# 001000-004.net
KiCad netlist of a schematic drawn in EAGLE
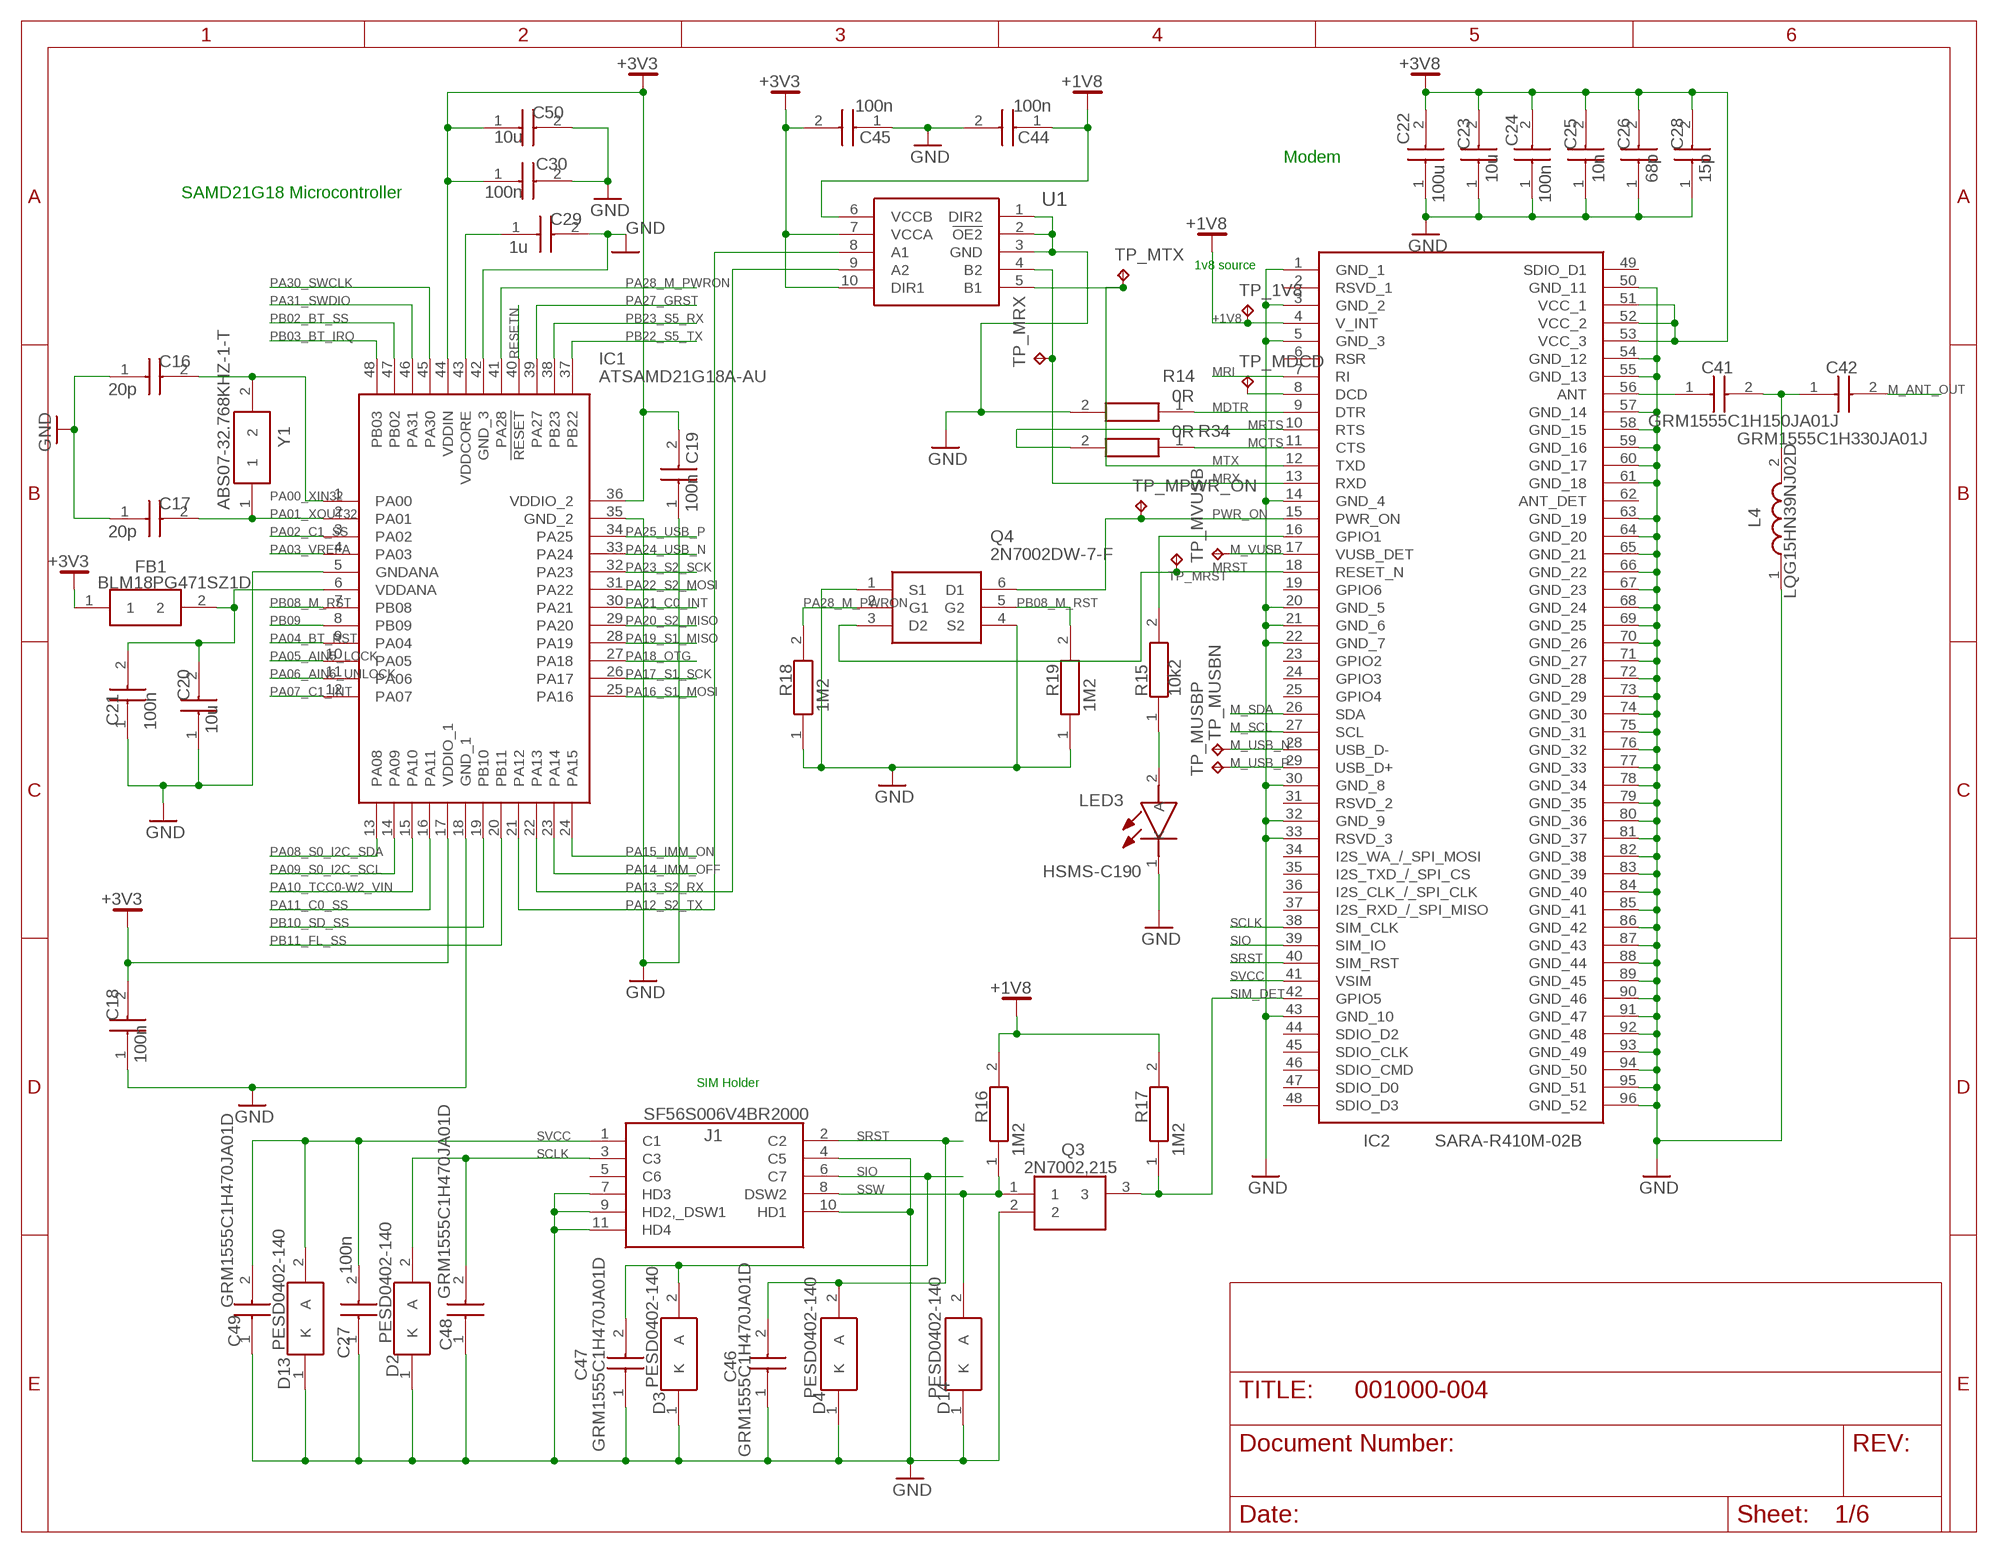
[diagram p0: schematic, sheet 1]
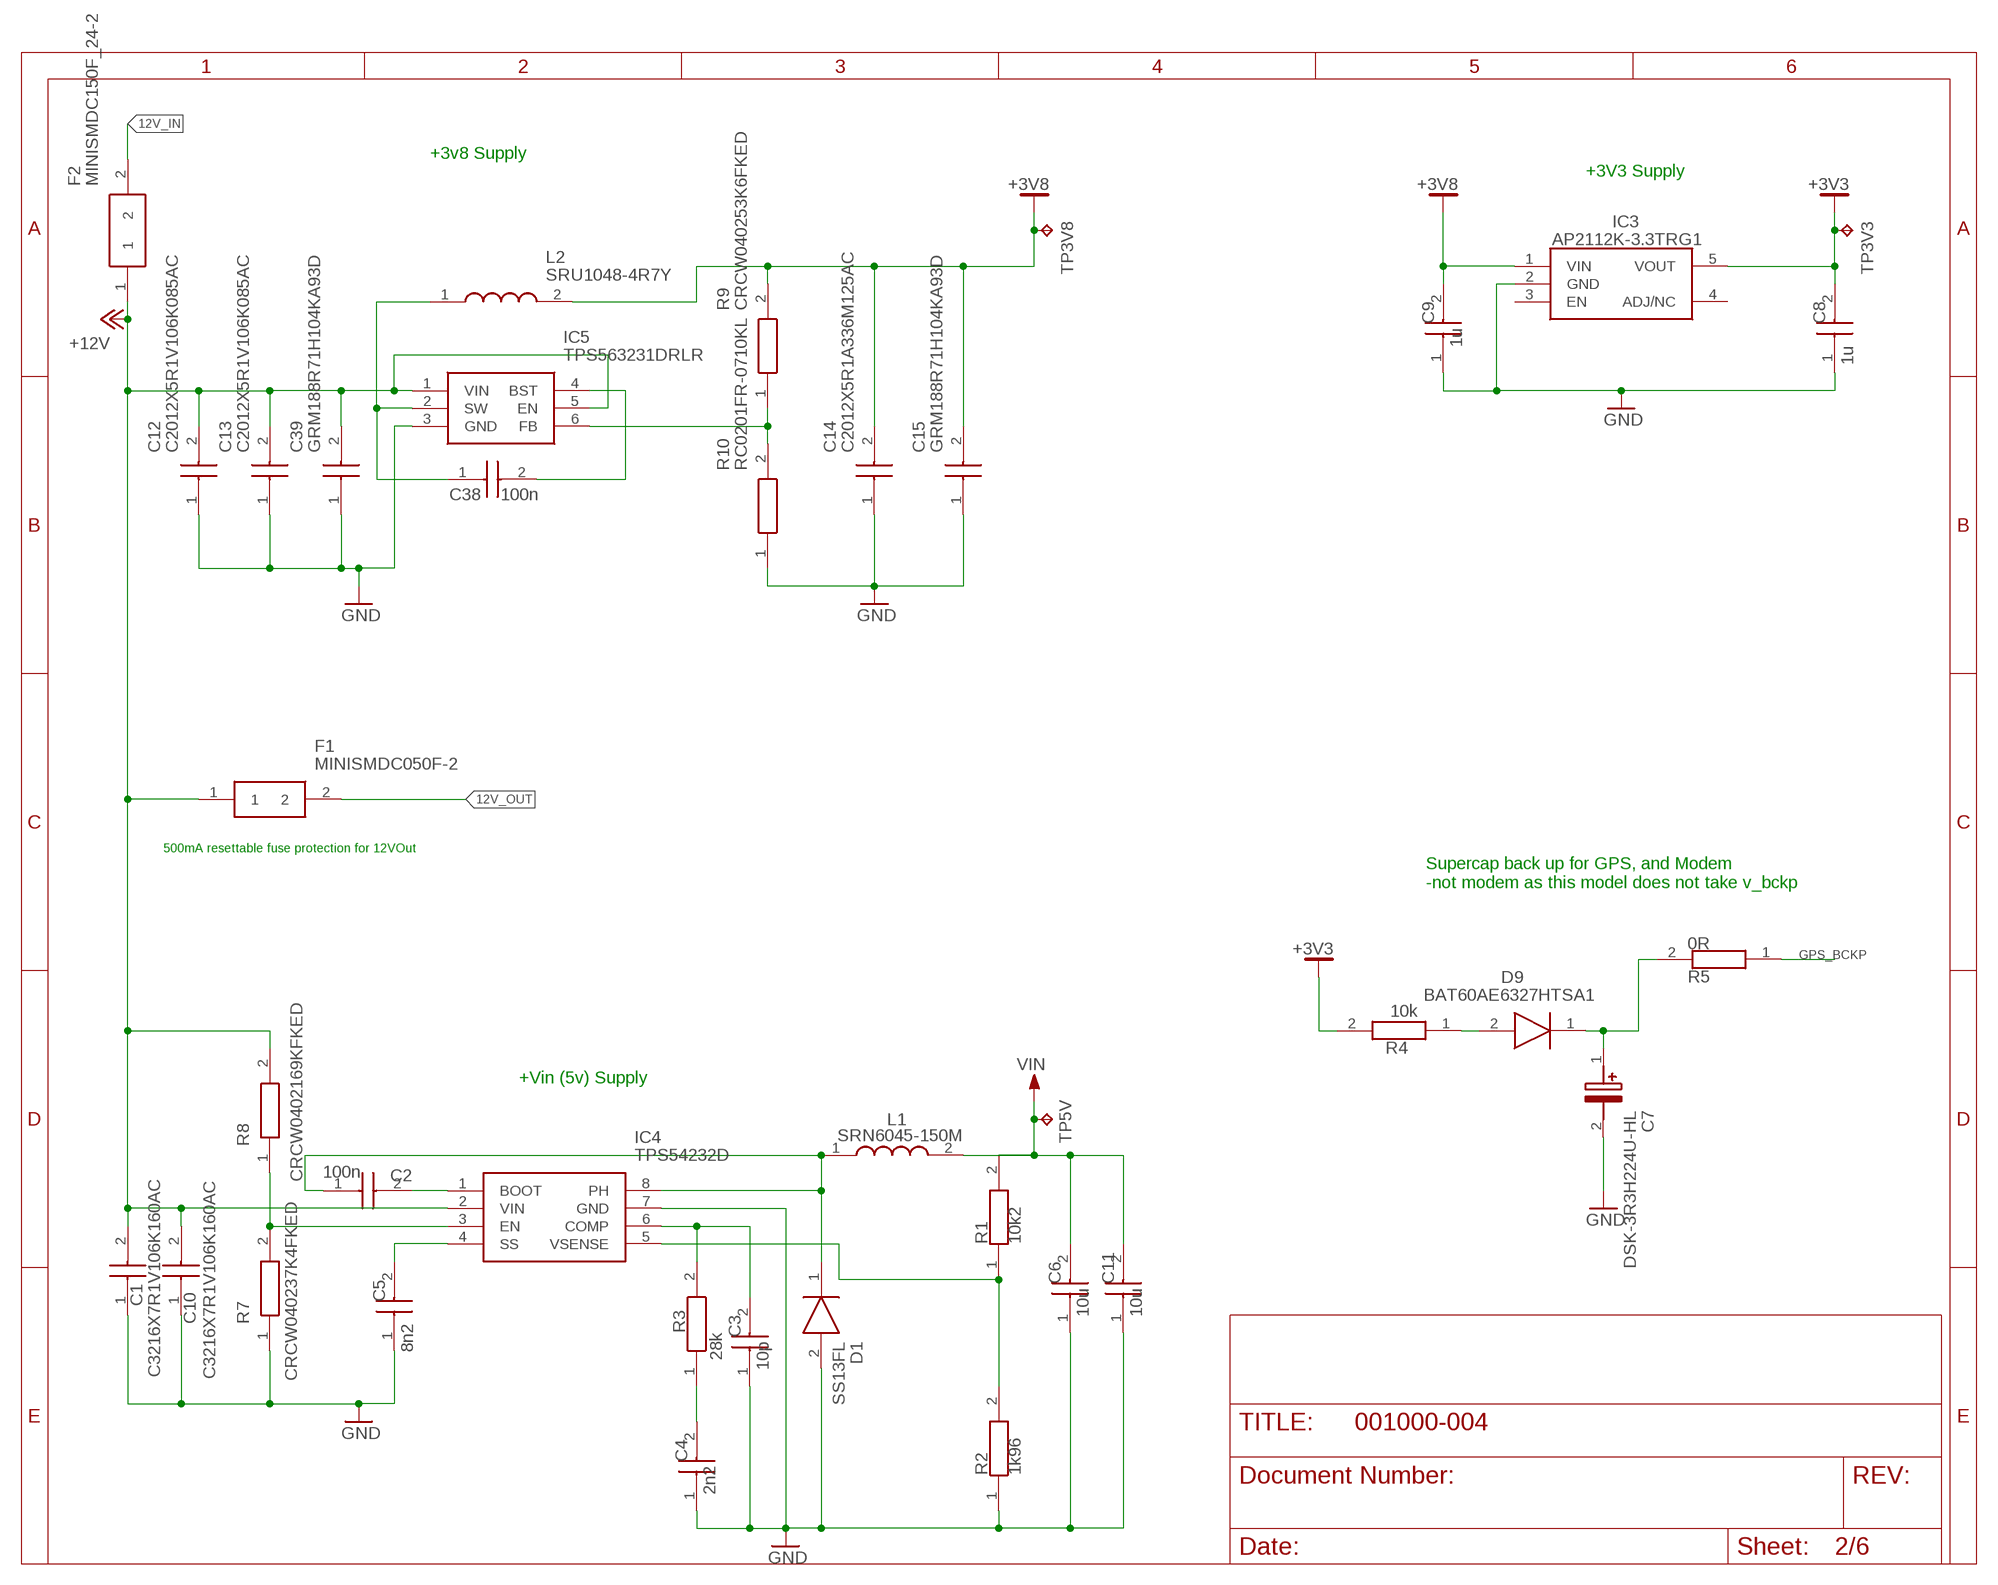
[diagram p1: schematic, sheet 2]
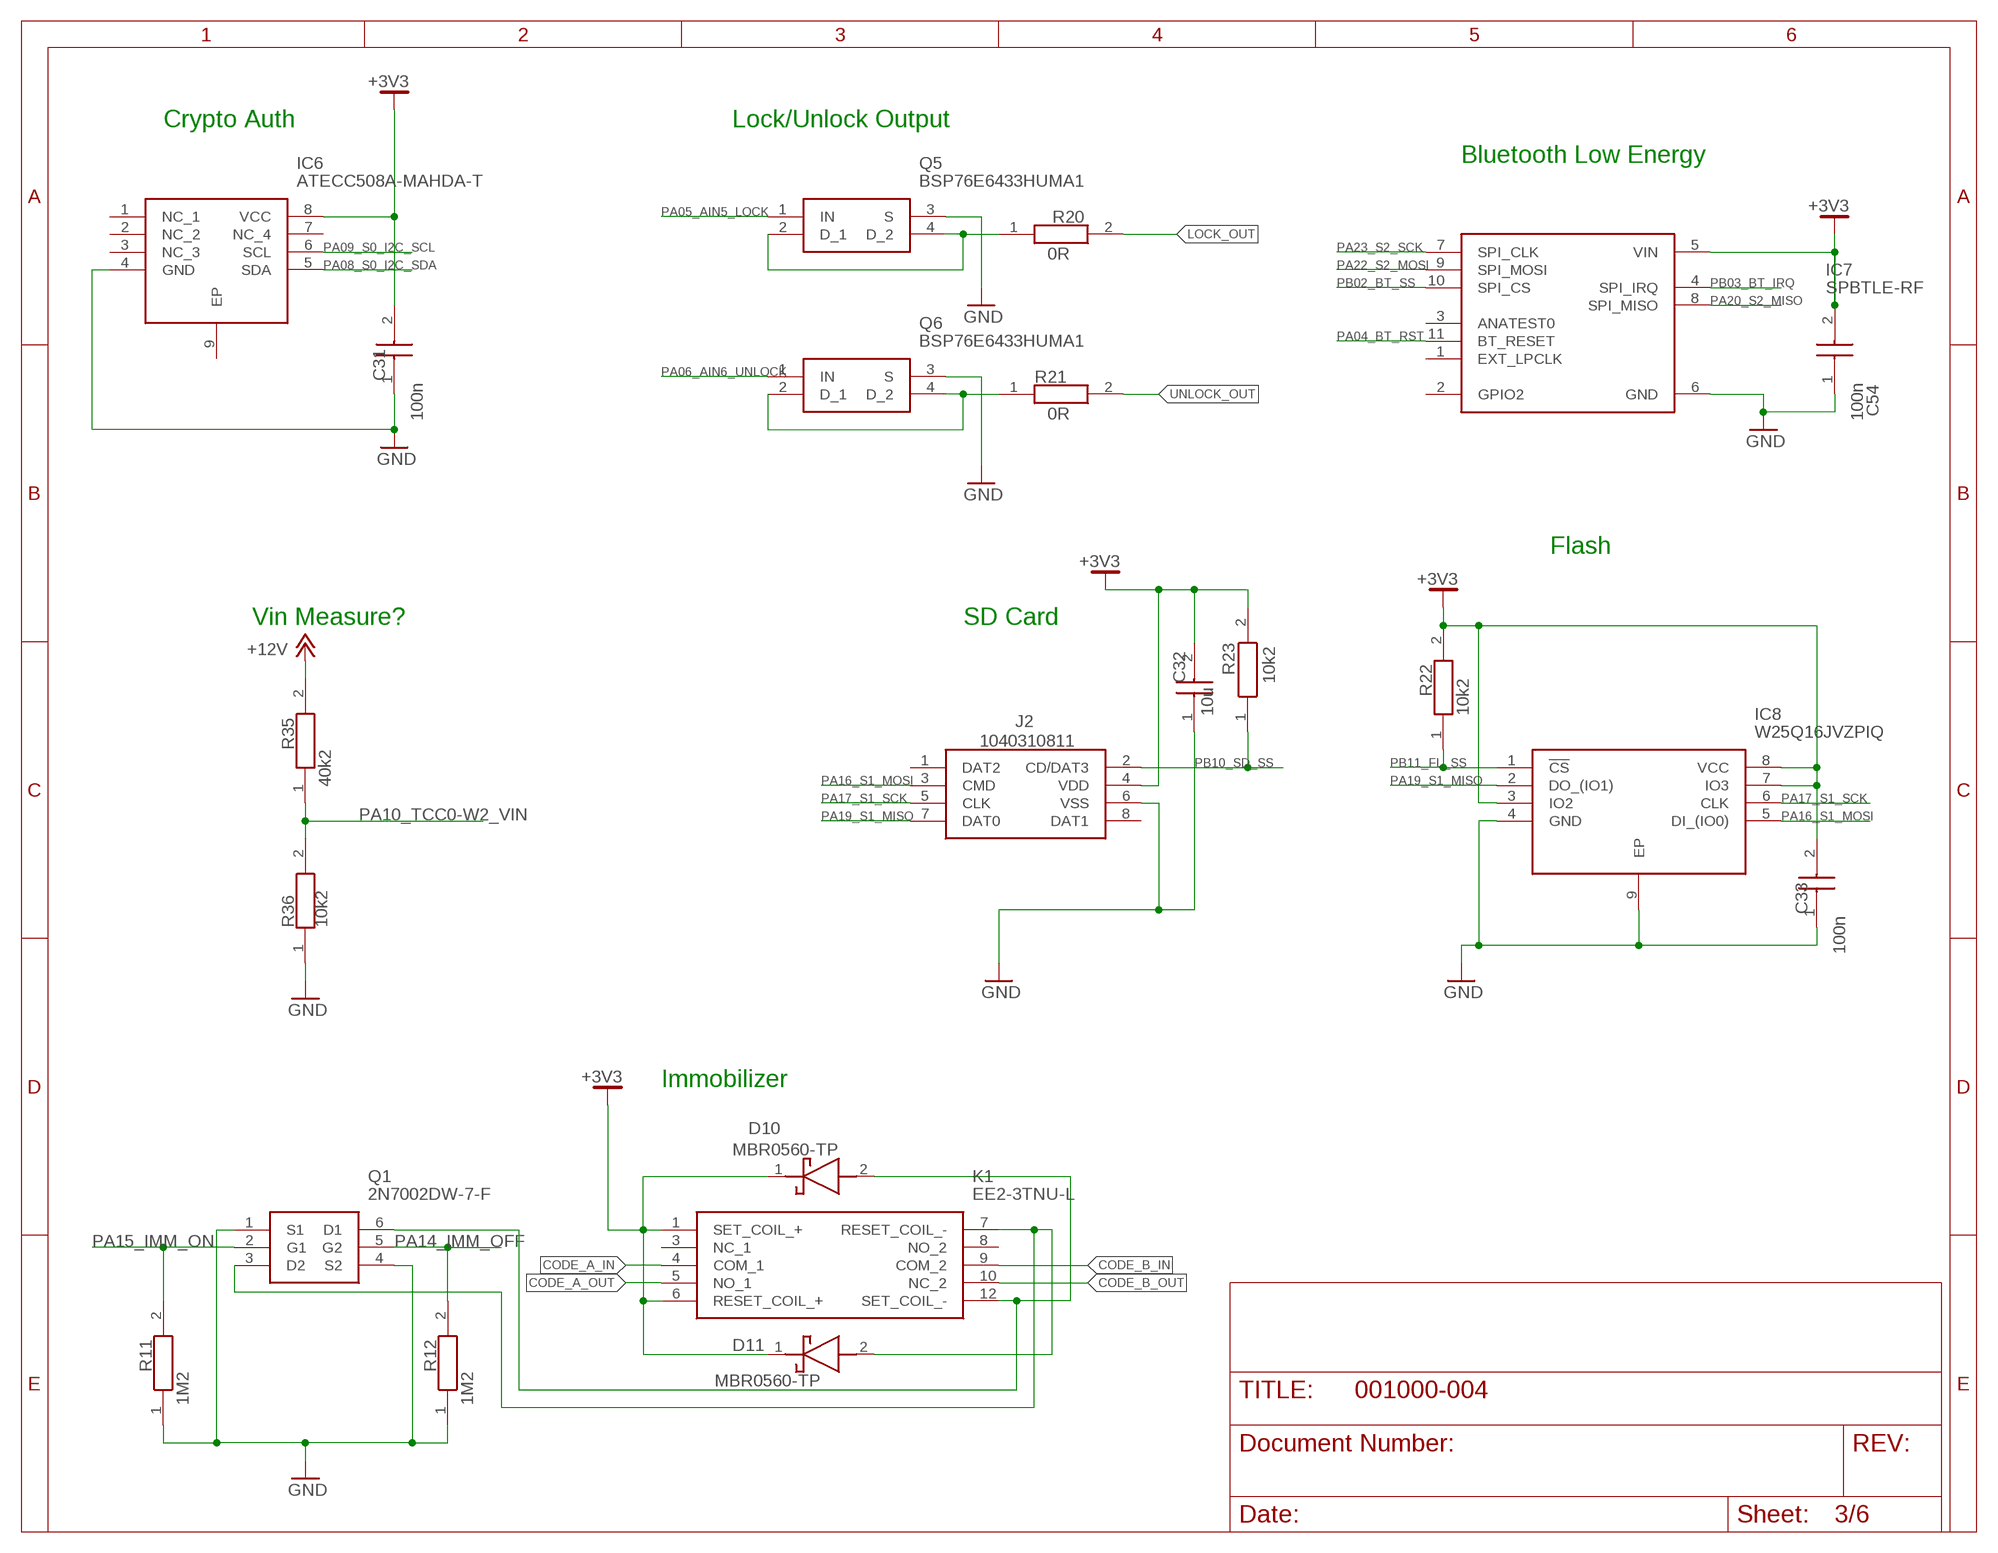
[diagram p2: schematic, sheet 3]
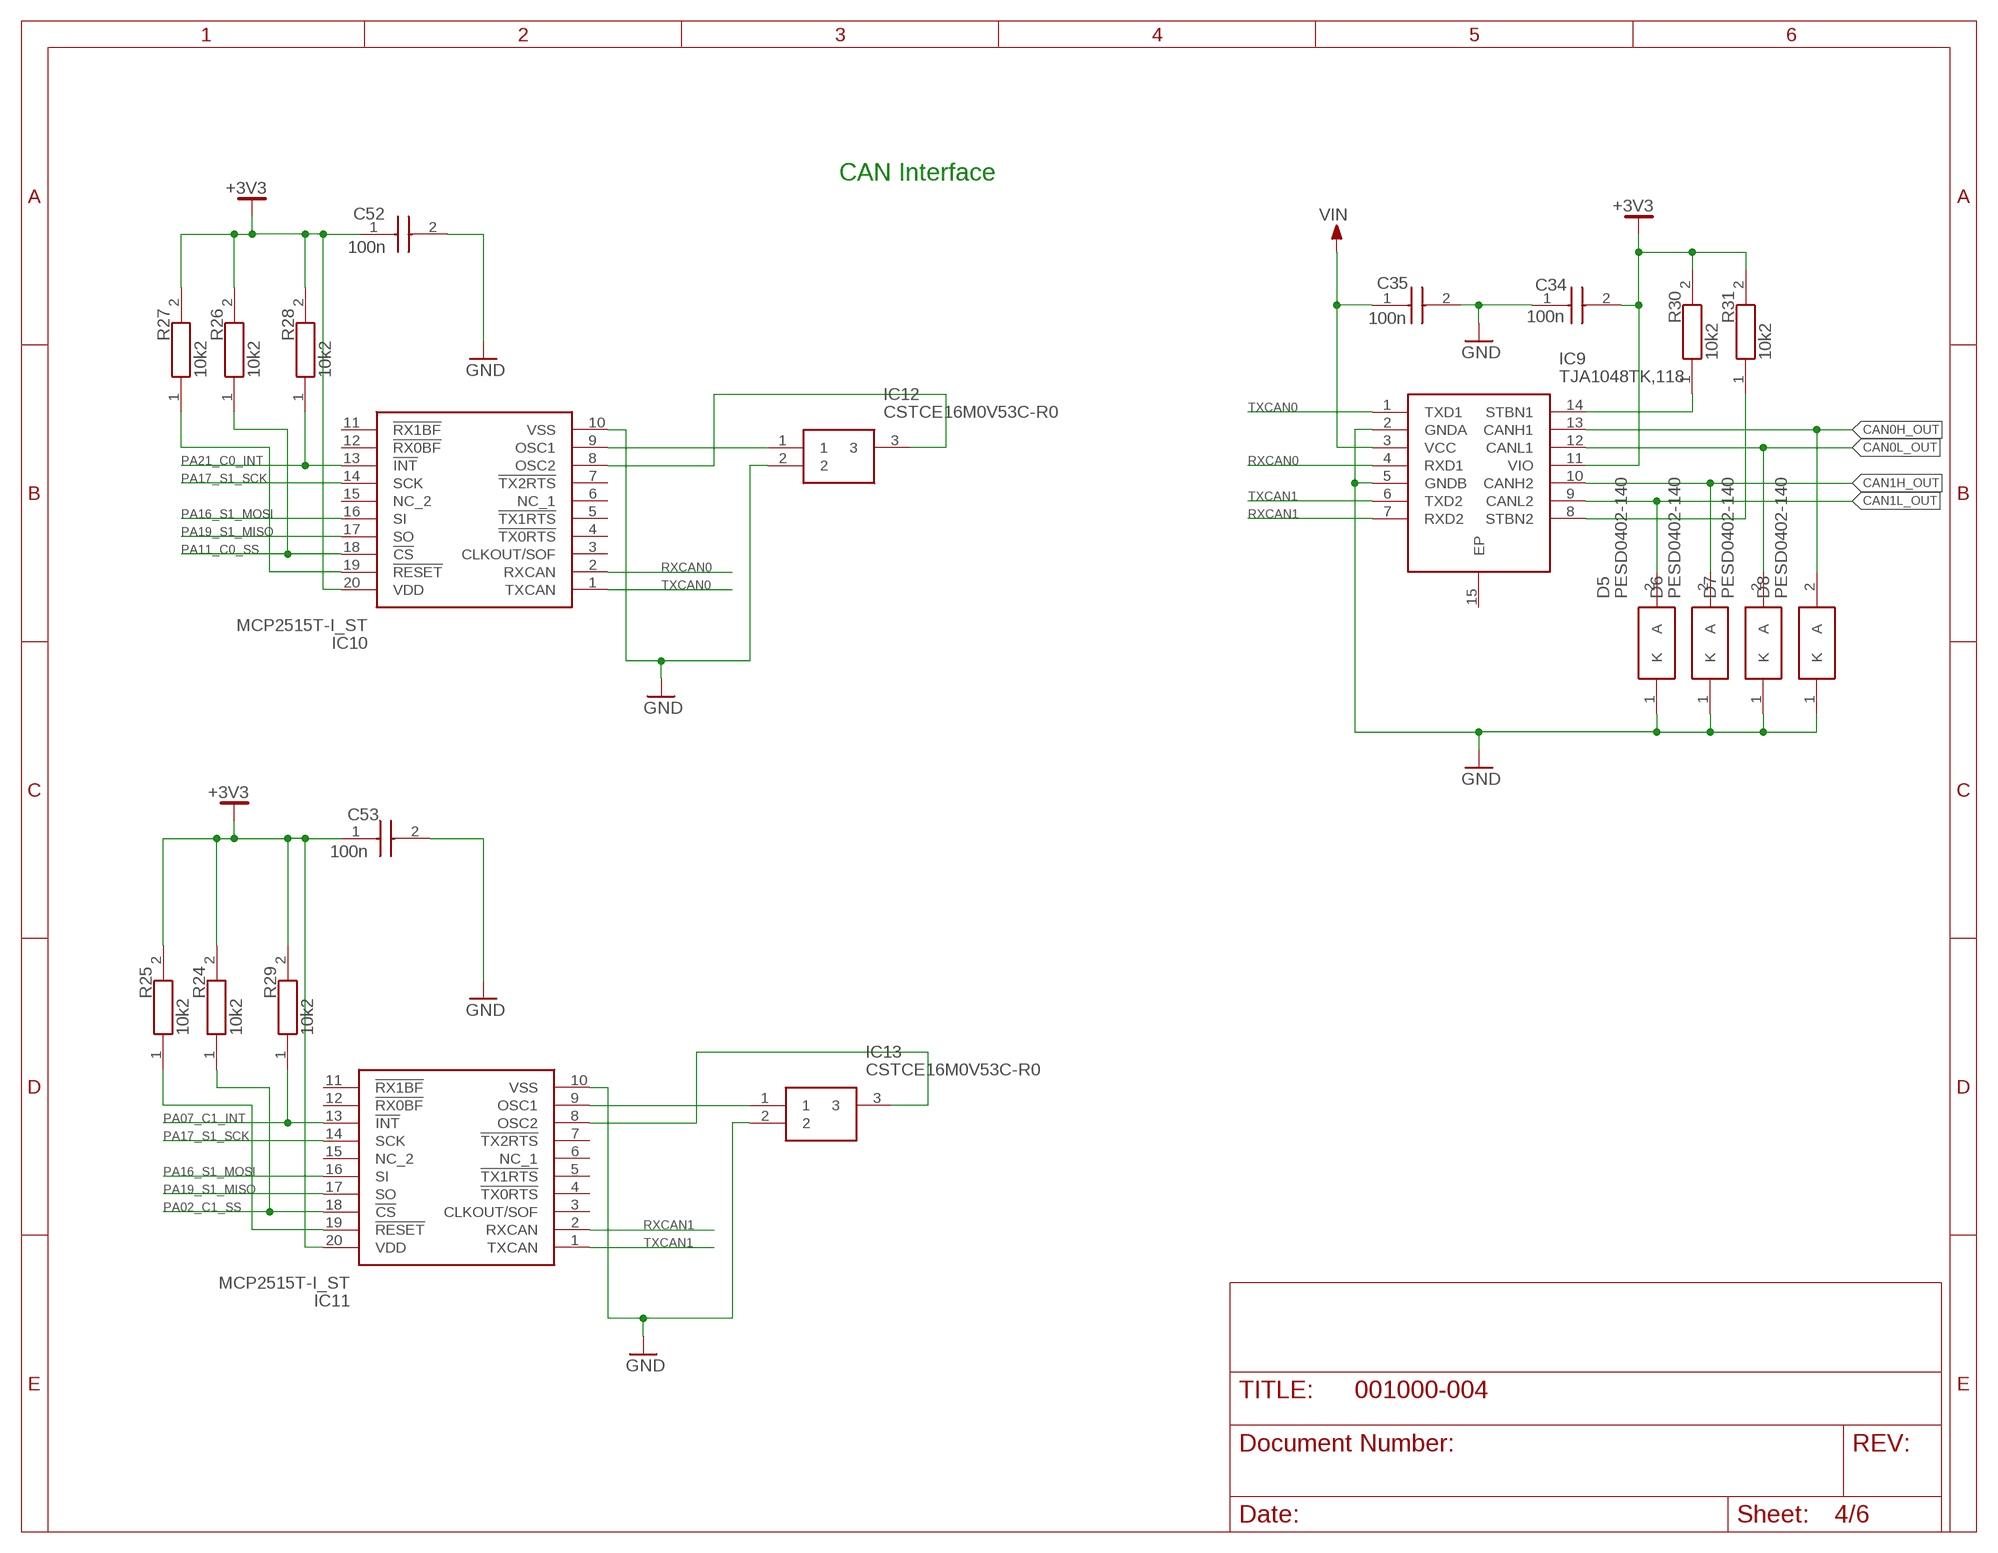
[diagram p3: schematic, sheet 4]
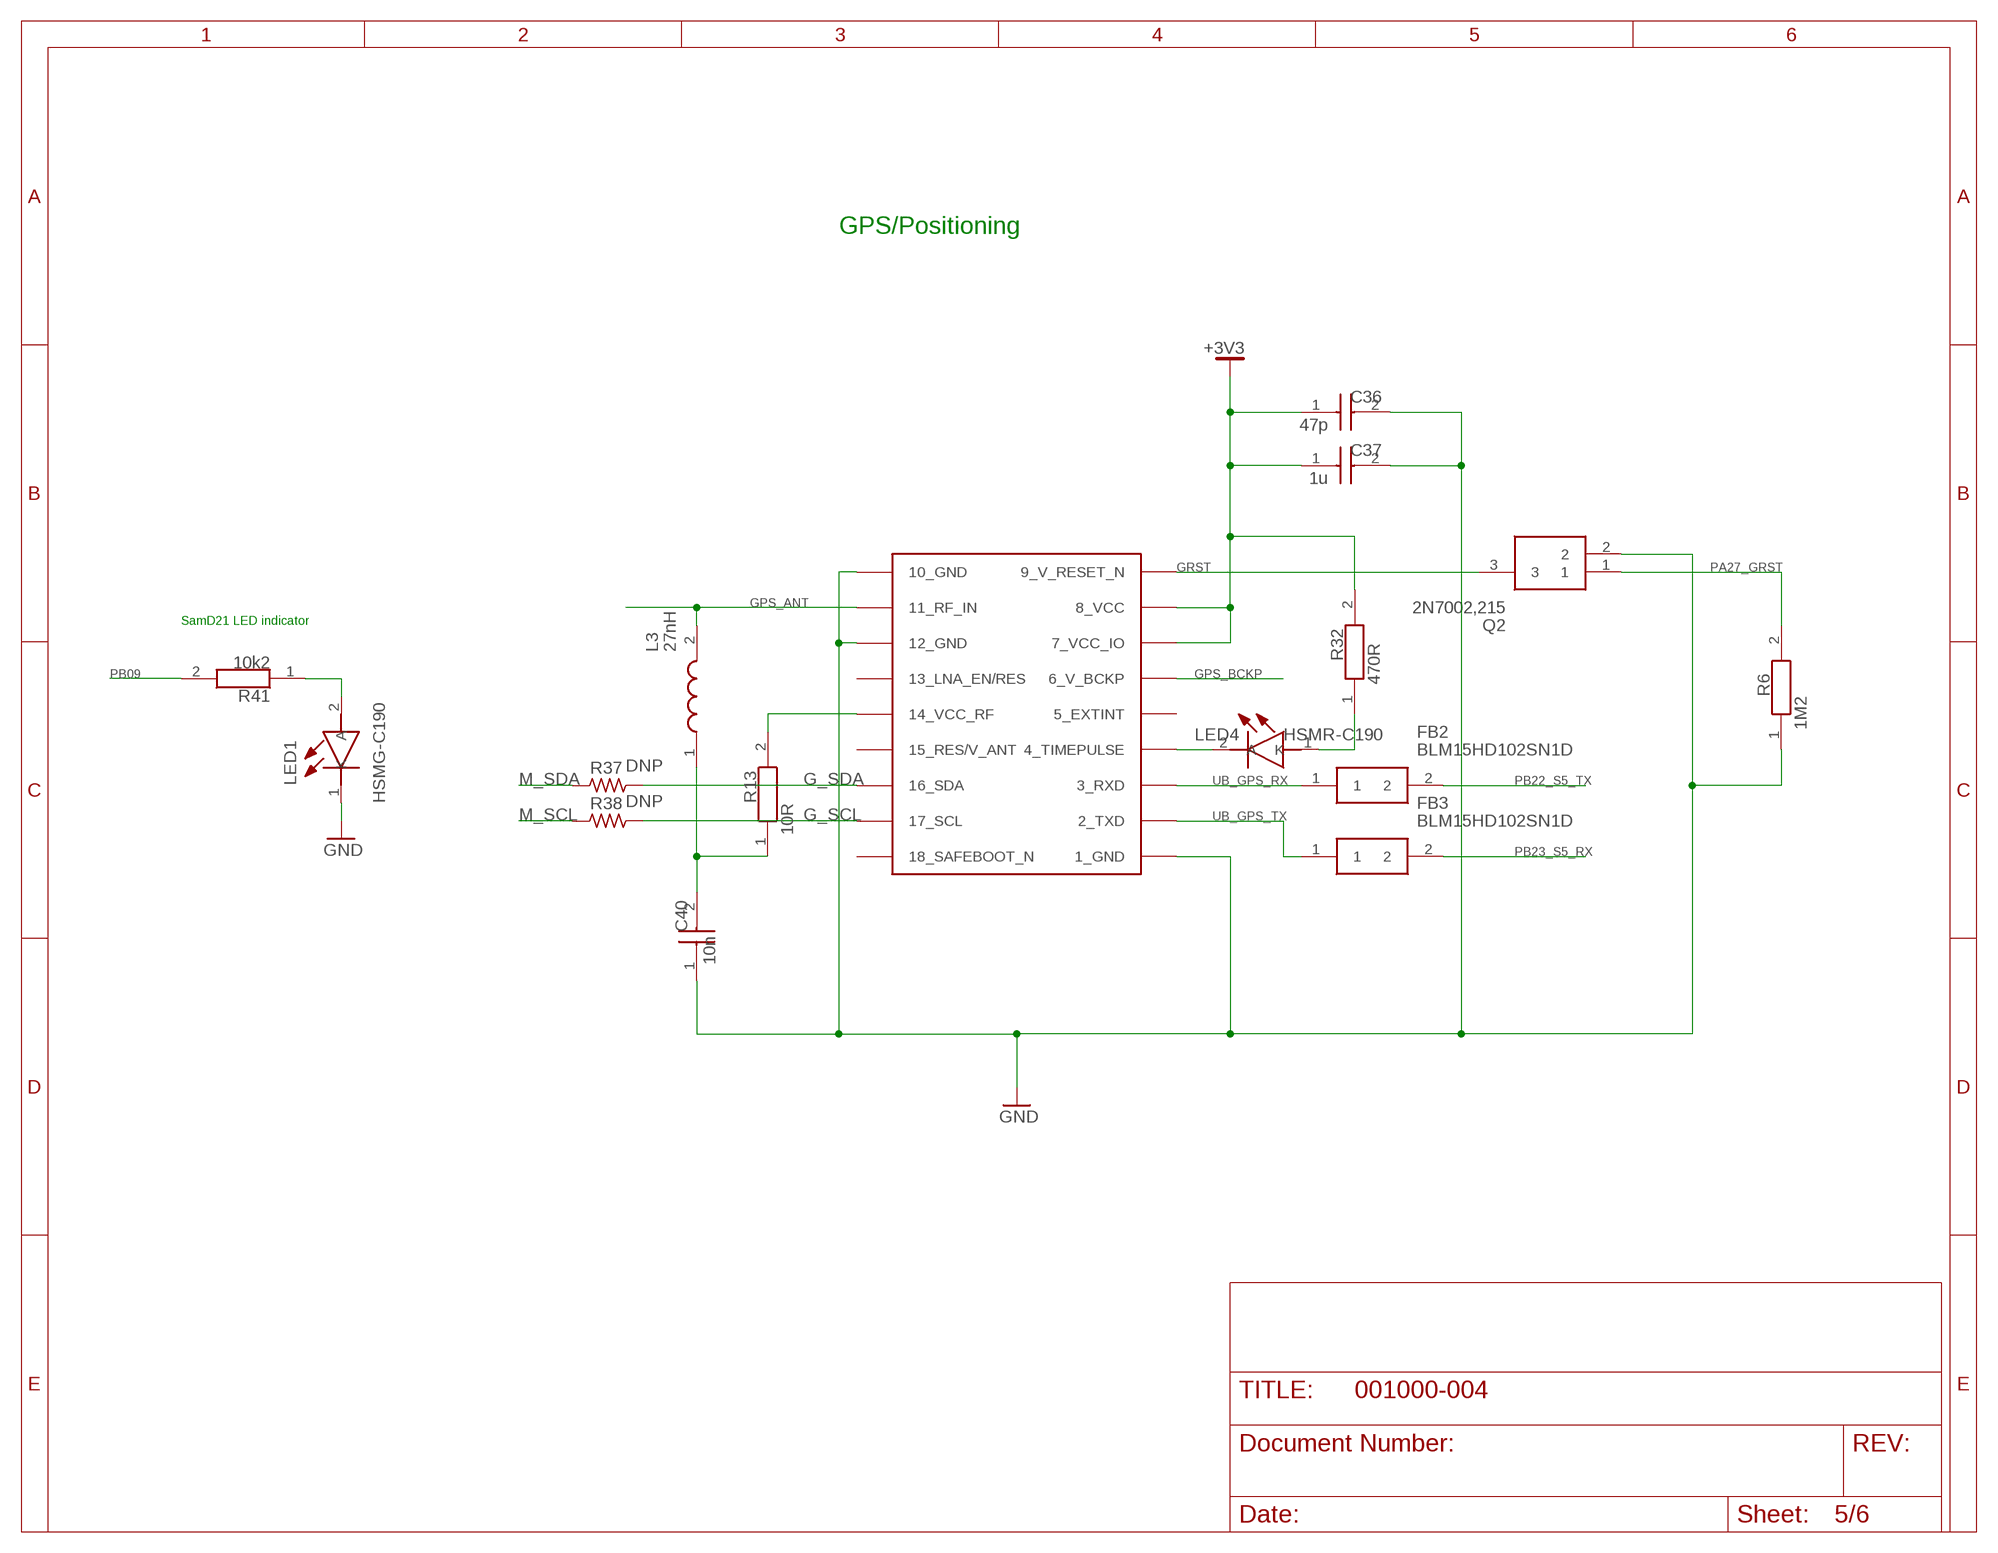
[diagram p4: schematic, sheet 5]
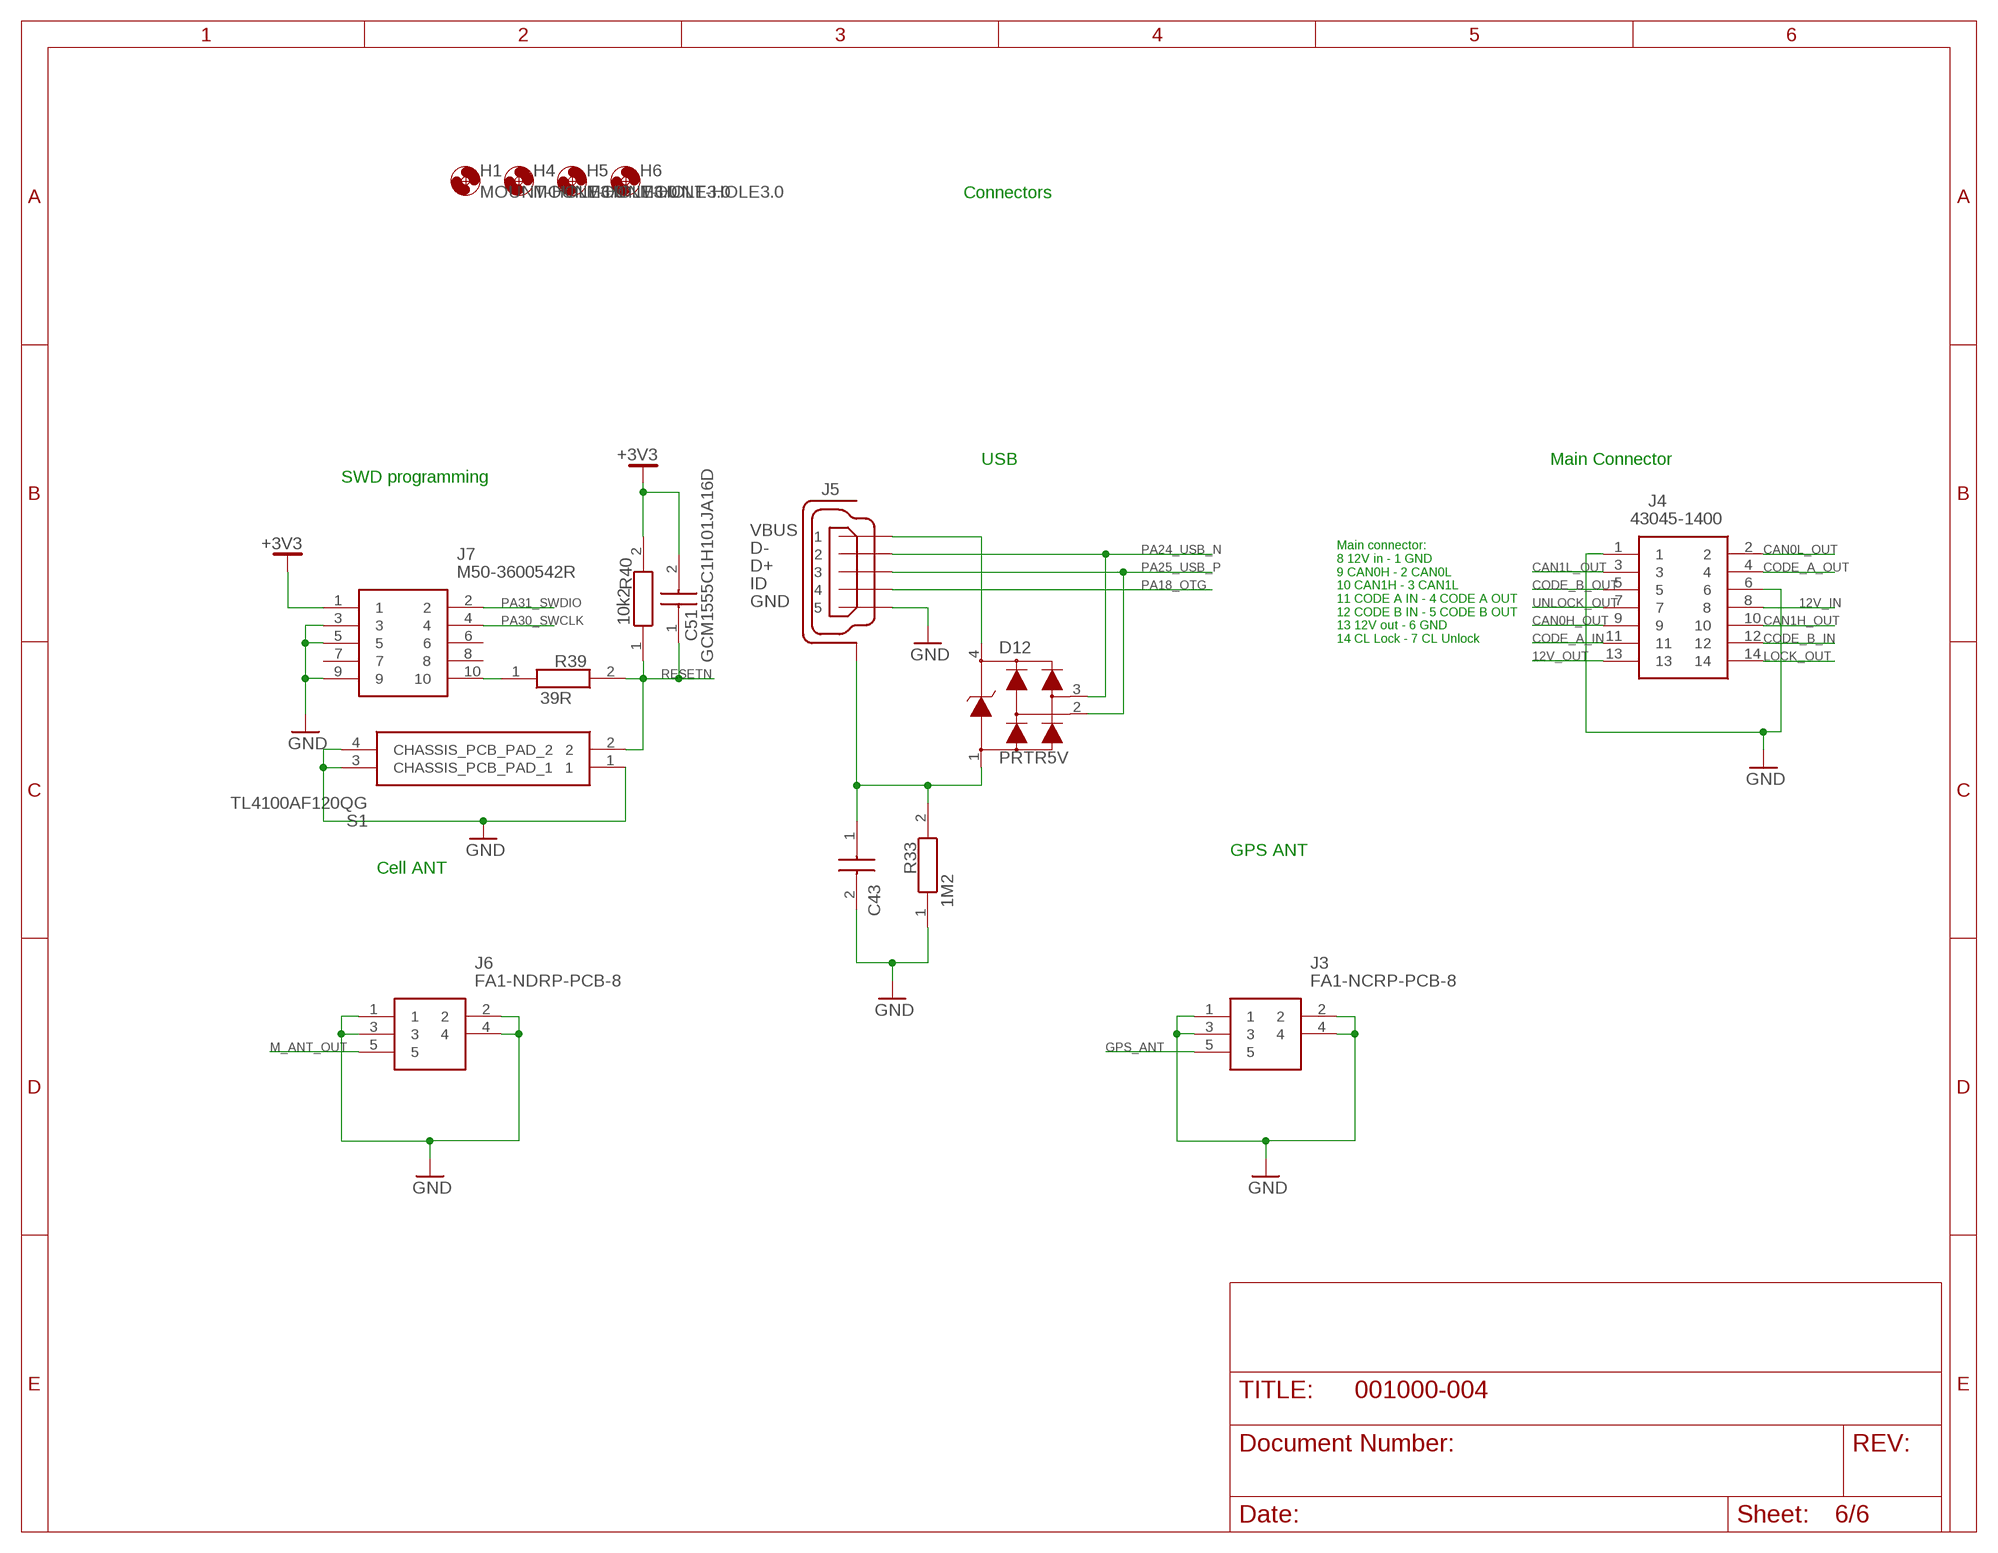
[diagram p5: schematic, sheet 6]

(export (version "E")
  (design (tool "Eeschema 10.0.6"))
  (components
    (comp (ref "C36")
      (value "47p")
      (footprint "eagle-import:CAPC1005X55N")
      (fields
        (field (name "MANUFACTURER_PART_NUMBER") "GRM1555C1H470JA01D")
        (field (name "MOUSER_PART_NUMBER") "81-GRM1555C1H470JA1D")
      )
      (libsource (lib "eagle-import") (part "GRM1555C1H470JA01D"))
    )
    (comp (ref "C37")
      (value "1u")
      (footprint "eagle-import:CAPC1608X90N")
      (fields
        (field (name "MANUFACTURER_PART_NUMBER") "GRT188C8YA105KE13D")
        (field (name "MOUSER_PART_NUMBER") "81-GRT188C8YA105KE3D")
      )
      (libsource (lib "eagle-import") (part "GRT188C8YA105KE13D"))
    )
    (comp (ref "C40")
      (value "10n")
      (footprint "eagle-import:CAPC1005X55N")
      (fields
        (field (name "MANUFACTURER_PART_NUMBER") "GCM155R71H103KA55D")
        (field (name "MOUSER_PART_NUMBER") "81-GCM155R71H103KA5D")
      )
      (libsource (lib "eagle-import") (part "GCM155R71H103KA55D"))
    )
    (comp (ref "FB2")
      (value "BLM15HD102SN1D")
      (footprint "eagle-import:BEADC1005X55N")
      (fields (field (name "MOUSER_PART_NUMBER") "81-BLM15HD102SN1D"))
      (libsource (lib "eagle-import") (part "BLM15HD102SN1D"))
    )
    (comp (ref "FB3")
      (value "BLM15HD102SN1D")
      (footprint "eagle-import:BEADC1005X55N")
      (fields (field (name "MOUSER_PART_NUMBER") "81-BLM15HD102SN1D"))
      (libsource (lib "eagle-import") (part "BLM15HD102SN1D"))
    )
    (comp (ref "L3")
      (value "27nH")
      (footprint "eagle-import:INDC1608X95N")
      (fields (field (name "MANUFACTURER_PART_NUMBER") "L-14C27NJV4T"))
      (libsource (lib "eagle-import") (part "L-14C27NJV4T"))
    )
    (comp (ref "LED1")
      (value "HSMG-C190")
      (footprint "eagle-import:LEDC1608X90N")
      (fields (field (name "MOUSER_PART_NUMBER") "630-HSMG-C190"))
      (libsource (lib "eagle-import") (part "HSMG-C190"))
    )
    (comp (ref "LED4")
      (value "HSMR-C190")
      (footprint "eagle-import:LEDC1608X80N")
      (fields (field (name "MOUSER_PART_NUMBER") "630-HSMR-C190"))
      (libsource (lib "eagle-import") (part "HSMR-C190"))
    )
    (comp (ref "Q2")
      (value "2N7002,215")
      (footprint "eagle-import:SOT95P230X110-3N")
      (fields (field (name "MOUSER_PART_NUMBER") "771-2N7002-T/R"))
      (libsource (lib "eagle-import") (part "2N7002,215"))
    )
    (comp (ref "R6")
      (value "1M2")
      (footprint "eagle-import:RESC1005X40N")
      (fields
        (field (name "MANUFACTURER_PART_NUMBER") "CRCW04021M20FKED")
        (field (name "MOUSER_PART_NUMBER") "71-CRCW04021M20FKED")
      )
      (libsource (lib "eagle-import") (part "CRCW04021M20FKED"))
    )
    (comp (ref "R13")
      (value "10R")
      (footprint "eagle-import:RESC1005X35N")
      (fields (field (name "MANUFACTURER_PART_NUMBER") "CRGCQ0402F10R"))
      (libsource (lib "eagle-import") (part "CRGCQ0402F10R"))
    )
    (comp (ref "R32")
      (value "470R")
      (footprint "eagle-import:RESC1005X35N")
      (fields (field (name "MANUFACTURER_PART_NUMBER") "CRGCQ0402J470R"))
      (libsource (lib "eagle-import") (part "CRGCQ0402J470R"))
    )
    (comp (ref "R37")
      (value "DNP")
      (footprint "eagle-import:R0402")
      (libsource (lib "eagle-import") (part "R_0402"))
    )
    (comp (ref "R38")
      (value "DNP")
      (footprint "eagle-import:R0402")
      (libsource (lib "eagle-import") (part "R_0402"))
    )
    (comp (ref "R41")
      (value "10k2")
      (footprint "eagle-import:RESC1005X40N")
      (fields
        (field (name "MANUFACTURER_PART_NUMBER") "CRCW040210K2FKED")
        (field (name "MOUSER_PART_NUMBER") "71-CRCW0402-10.2K-E3")
      )
      (libsource (lib "eagle-import") (part "CRCW040210K2FKED"))
    )
    (comp (ref "U$1")
      (value "MAX-M8")
      (footprint "eagle-import:MAX-M8")
      (libsource (lib "eagle-import") (part "MAX-M8"))
    )
    (comp (ref "C1")
      (value "C3216X7R1V106K160AC")
      (footprint "eagle-import:CAPC3216X180N")
      (fields (field (name "MOUSER_PART_NUMBER") "810-C3216X7R1V106KAC"))
      (libsource (lib "eagle-import") (part "C3216X7R1V106K160AC"))
    )
    (comp (ref "C2")
      (value "100n")
      (footprint "eagle-import:CAPC1005X55N")
      (fields (field (name "MANUFACTURER_PART_NUMBER") "GCM155R71C104KA55J"))
      (libsource (lib "eagle-import") (part "GCM155R71C104KA55J"))
    )
    (comp (ref "C3")
      (value "10p")
      (footprint "eagle-import:CAPC1005X55N")
      (fields (field (name "MANUFACTURER_PART_NUMBER") "GCM1555C1H100JA16D"))
      (libsource (lib "eagle-import") (part "GCM1555C1H100JA16D"))
    )
    (comp (ref "C4")
      (value "2n2")
      (footprint "eagle-import:CAPC1005X55N")
      (fields
        (field (name "MANUFACTURER_PART_NUMBER") "GRM155R71H222KA01D")
        (field (name "MOUSER_PART_NUMBER") "81-GRM36X222K50")
      )
      (libsource (lib "eagle-import") (part "GRM155R71H222KA01D"))
    )
    (comp (ref "C5")
      (value "8n2")
      (footprint "eagle-import:CAPC1005X55N")
      (fields
        (field (name "MANUFACTURER_PART_NUMBER") "GRM155R71C822KA01D")
        (field (name "MOUSER_PART_NUMBER") "81-GRM155R71C822KA1D")
      )
      (libsource (lib "eagle-import") (part "GRM155R71C822KA01D"))
    )
    (comp (ref "C6")
      (value "10u")
      (footprint "eagle-import:CAPC2012X145N")
      (fields
        (field (name "MANUFACTURER_PART_NUMBER") "GRM21BC81C106KE15L")
        (field (name "MOUSER_PART_NUMBER") "81-GRM21BC81C106KE5L")
      )
      (libsource (lib "eagle-import") (part "GRM21BC81C106KE15L"))
    )
    (comp (ref "C7")
      (value "DSK-3R3H224U-HL")
      (footprint "eagle-import:DSK-414_HL")
      (fields (field (name "MOUSER_PART_NUMBER") "555-DSK3R3H224U-HL"))
      (libsource (lib "eagle-import") (part "DSK-3R3H224U-HL"))
    )
    (comp (ref "C8")
      (value "1u")
      (footprint "eagle-import:CAPC1005X55N")
      (fields
        (field (name "MANUFACTURER_PART_NUMBER") "GRM155R61C105MA12D")
        (field (name "MOUSER_PART_NUMBER") "81-GRM155R61C105MA2D")
      )
      (libsource (lib "eagle-import") (part "GRM155R61C105MA12D"))
    )
    (comp (ref "C9")
      (value "1u")
      (footprint "eagle-import:CAPC1005X55N")
      (fields
        (field (name "MANUFACTURER_PART_NUMBER") "GRM155R61C105MA12D")
        (field (name "MOUSER_PART_NUMBER") "81-GRM155R61C105MA2D")
      )
      (libsource (lib "eagle-import") (part "GRM155R61C105MA12D"))
    )
    (comp (ref "C10")
      (value "C3216X7R1V106K160AC")
      (footprint "eagle-import:CAPC3216X180N")
      (fields (field (name "MOUSER_PART_NUMBER") "810-C3216X7R1V106KAC"))
      (libsource (lib "eagle-import") (part "C3216X7R1V106K160AC"))
    )
    (comp (ref "C11")
      (value "10u")
      (footprint "eagle-import:CAPC2012X145N")
      (fields
        (field (name "MANUFACTURER_PART_NUMBER") "GRM21BC81C106KE15L")
        (field (name "MOUSER_PART_NUMBER") "81-GRM21BC81C106KE5L")
      )
      (libsource (lib "eagle-import") (part "GRM21BC81C106KE15L"))
    )
    (comp (ref "C12")
      (value "C2012X5R1V106K085AC")
      (footprint "eagle-import:CAPC2012X100N")
      (fields (field (name "MOUSER_PART_NUMBER") "810-C2012X5R1V106K0C"))
      (libsource (lib "eagle-import") (part "C2012X5R1V106K085AC"))
    )
    (comp (ref "C13")
      (value "C2012X5R1V106K085AC")
      (footprint "eagle-import:CAPC2012X100N")
      (fields (field (name "MOUSER_PART_NUMBER") "810-C2012X5R1V106K0C"))
      (libsource (lib "eagle-import") (part "C2012X5R1V106K085AC"))
    )
    (comp (ref "C14")
      (value "C2012X5R1A336M125AC")
      (footprint "eagle-import:CAPC2012X145N")
      (fields (field (name "MOUSER_PART_NUMBER") "810-C2012X5R1A336M"))
      (libsource (lib "eagle-import") (part "C2012X5R1A336M125AC"))
    )
    (comp (ref "C15")
      (value "GRM188R71H104KA93D")
      (footprint "eagle-import:CAPC1608X90N")
      (fields (field (name "MOUSER_PART_NUMBER") "81-GRM39X104K50D"))
      (libsource (lib "eagle-import") (part "GRM188R71H104KA93D"))
    )
    (comp (ref "C38")
      (value "100n")
      (footprint "eagle-import:CAPC1005X55N")
      (fields (field (name "MANUFACTURER_PART_NUMBER") "GCM155R71C104KA55J"))
      (libsource (lib "eagle-import") (part "GCM155R71C104KA55J"))
    )
    (comp (ref "C39")
      (value "GRM188R71H104KA93D")
      (footprint "eagle-import:CAPC1608X90N")
      (fields (field (name "MOUSER_PART_NUMBER") "81-GRM39X104K50D"))
      (libsource (lib "eagle-import") (part "GRM188R71H104KA93D"))
    )
    (comp (ref "D1")
      (value "SS13FL")
      (footprint "eagle-import:SODFL3617X108N")
      (fields (field (name "MOUSER_PART_NUMBER") "512-SS13FL"))
      (libsource (lib "eagle-import") (part "SS13FL"))
    )
    (comp (ref "D9")
      (value "BAT60AE6327HTSA1")
      (footprint "eagle-import:SOD2513X110N")
      (fields (field (name "MOUSER_PART_NUMBER") "726-BAT60AE6327HTSA1"))
      (libsource (lib "eagle-import") (part "BAT60AE6327HTSA1"))
    )
    (comp (ref "F1")
      (value "MINISMDC050F-2")
      (footprint "eagle-import:FUSC4632X62N")
      (fields (field (name "MOUSER_PART_NUMBER") "650-MINISMDC050F-2"))
      (libsource (lib "eagle-import") (part "MINISMDC050F-2"))
    )
    (comp (ref "F2")
      (value "MINISMDC150F_24-2")
      (footprint "eagle-import:FUSC4632X194N")
      (fields
        (field (name "MANUFACTURER_PART_NUMBER") "MINISMDC150F/24-2")
        (field (name "MOUSER_PART_NUMBER") "650-MINISMDC150F/24")
      )
      (libsource (lib "eagle-import") (part "MINISMDC150F_24-2"))
    )
    (comp (ref "IC3")
      (value "AP2112K-3.3TRG1")
      (footprint "eagle-import:SOT95P282X130-5N")
      (fields (field (name "MOUSER_PART_NUMBER") "621-AP2112K-3.3TRG1"))
      (libsource (lib "eagle-import") (part "AP2112K-3.3TRG1"))
    )
    (comp (ref "IC4")
      (value "TPS54232D")
      (footprint "eagle-import:SOIC127P600X175-8N")
      (fields (field (name "MOUSER_PART_NUMBER") "595-TPS54232D"))
      (libsource (lib "eagle-import") (part "TPS54232D"))
    )
    (comp (ref "IC5")
      (value "TPS563231DRLR")
      (footprint "eagle-import:SOTFL50P160X60-6N")
      (fields (field (name "MOUSER_PART_NUMBER") "595-TPS563231DRLR"))
      (libsource (lib "eagle-import") (part "TPS563231DRLR"))
    )
    (comp (ref "L1")
      (value "SRN6045-150M")
      (footprint "eagle-import:SRN6045_1")
      (fields (field (name "MOUSER_PART_NUMBER") "652-SRN6045-150M"))
      (libsource (lib "eagle-import") (part "SRN6045-150M"))
    )
    (comp (ref "L2")
      (value "SRU1048-4R7Y")
      (footprint "eagle-import:SRU10484R7Y")
      (fields (field (name "MOUSER_PART_NUMBER") "652-SRU1048-4R7Y"))
      (libsource (lib "eagle-import") (part "SRU1048-4R7Y"))
    )
    (comp (ref "R1")
      (value "10k2")
      (footprint "eagle-import:RESC1005X40N")
      (fields
        (field (name "MANUFACTURER_PART_NUMBER") "CRCW040210K2FKED")
        (field (name "MOUSER_PART_NUMBER") "71-CRCW0402-10.2K-E3")
      )
      (libsource (lib "eagle-import") (part "CRCW040210K2FKED"))
    )
    (comp (ref "R2")
      (value "1k96")
      (footprint "eagle-import:RESC1005X40N")
      (fields
        (field (name "MANUFACTURER_PART_NUMBER") "CRCW04021K96FKED")
        (field (name "MOUSER_PART_NUMBER") "71-CRCW0402-1.96K-E3")
      )
      (libsource (lib "eagle-import") (part "CRCW04021K96FKED"))
    )
    (comp (ref "R3")
      (value "28k")
      (footprint "eagle-import:RESC1005X40N")
      (fields
        (field (name "MANUFACTURER_PART_NUMBER") "CRCW040228K0FKED")
        (field (name "MOUSER_PART_NUMBER") "71-CRCW0402-28K-E3")
      )
      (libsource (lib "eagle-import") (part "CRCW040228K0FKED"))
    )
    (comp (ref "R4")
      (value "10k")
      (footprint "eagle-import:RESC1508X50N")
      (fields (field (name "MANUFACTURER_PART_NUMBER") "RNCP0603FTD10K0"))
      (libsource (lib "eagle-import") (part "RNCP0603FTD10K0"))
    )
    (comp (ref "R5")
      (value "0R")
      (footprint "eagle-import:RESC1005X40N")
      (fields (field (name "MANUFACTURER_PART_NUMBER") "RMCF0402ZT0R00"))
      (libsource (lib "eagle-import") (part "RMCF0402ZT0R00"))
    )
    (comp (ref "R7")
      (value "CRCW040237K4FKED")
      (footprint "eagle-import:RESC1005X40N")
      (fields (field (name "MOUSER_PART_NUMBER") "71-CRCW0402-37.4K-E3"))
      (libsource (lib "eagle-import") (part "CRCW040237K4FKED"))
    )
    (comp (ref "R8")
      (value "CRCW0402169KFKED")
      (footprint "eagle-import:RESC1005X40N")
      (fields (field (name "MOUSER_PART_NUMBER") "71-CRCW0402-169K-E3"))
      (libsource (lib "eagle-import") (part "CRCW0402169KFKED"))
    )
    (comp (ref "R9")
      (value "CRCW040253K6FKED")
      (footprint "eagle-import:RESC1005X40N")
      (fields (field (name "MOUSER_PART_NUMBER") "71-CRCW0402-53.6K-E3"))
      (libsource (lib "eagle-import") (part "CRCW040253K6FKED"))
    )
    (comp (ref "R10")
      (value "RC0201FR-0710KL")
      (footprint "eagle-import:RESC0603X26N")
      (fields (field (name "MOUSER_PART_NUMBER") "603-RC0201FR-0710KL"))
      (libsource (lib "eagle-import") (part "RC0201FR-0710KL"))
    )
    (comp (ref "TP3V3")
      (value "TPB1,27")
      (footprint "eagle-import:B1,27")
      (libsource (lib "eagle-import") (part "TPB1,27"))
    )
    (comp (ref "TP3V8")
      (value "TPB1,27")
      (footprint "eagle-import:B1,27")
      (libsource (lib "eagle-import") (part "TPB1,27"))
    )
    (comp (ref "TP5V")
      (value "TPB1,27")
      (footprint "eagle-import:B1,27")
      (libsource (lib "eagle-import") (part "TPB1,27"))
    )
    (comp (ref "C43")
      (value "4n7")
      (footprint "eagle-import:CAPC1005X55N")
      (fields
        (field (name "MANUFACTURER_PART_NUMBER") "GRM155R71H472KA01J")
        (field (name "MOUSER_PART_NUMBER") "81-GRM155R71H472KA1J")
      )
      (libsource (lib "eagle-import") (part "GRM155R71H472KA01J"))
    )
    (comp (ref "C51")
      (value "GCM1555C1H101JA16D")
      (footprint "eagle-import:CAPC1005X55N")
      (libsource (lib "eagle-import") (part "GCM1555C1H101JA16D"))
    )
    (comp (ref "D12")
      (value "PRTR5V")
      (footprint "eagle-import:SOT190P230X110-4N")
      (fields (field (name "MANUFACTURER") "NXP"))
      (libsource (lib "eagle-import") (part "PRTR5V0U2X,215"))
    )
    (comp (ref "H1")
      (value "MOUNT-HOLE3.0")
      (footprint "eagle-import:3,0")
      (libsource (lib "eagle-import") (part "MOUNT-HOLE3.0"))
    )
    (comp (ref "H4")
      (value "MOUNT-HOLE3.0")
      (footprint "eagle-import:3,0")
      (libsource (lib "eagle-import") (part "MOUNT-HOLE3.0"))
    )
    (comp (ref "H5")
      (value "MOUNT-HOLE3.0")
      (footprint "eagle-import:3,0")
      (libsource (lib "eagle-import") (part "MOUNT-HOLE3.0"))
    )
    (comp (ref "H6")
      (value "MOUNT-HOLE3.0")
      (footprint "eagle-import:3,0")
      (libsource (lib "eagle-import") (part "MOUNT-HOLE3.0"))
    )
    (comp (ref "J3")
      (value "FA1-NCRP-PCB-8")
      (footprint "eagle-import:FA1NCRPPCB8")
      (fields (field (name "MOUSER_PART_NUMBER") "523-FA1-NCRP-PCB-8"))
      (libsource (lib "eagle-import") (part "FA1-NCRP-PCB-8"))
    )
    (comp (ref "J4")
      (value "43045-1400")
      (footprint "eagle-import:43045-1400")
      (fields (field (name "MOUSER_PART_NUMBER") "538-43045-1400"))
      (libsource (lib "eagle-import") (part "43045-1400"))
    )
    (comp (ref "J5")
      (value "-")
      (footprint "eagle-import:ZX62-AB-5PA")
      (fields (field (name "MANUFACTURER") "Hirose"))
      (libsource (lib "eagle-import") (part "USB-MICRO"))
    )
    (comp (ref "J6")
      (value "FA1-NDRP-PCB-8")
      (footprint "eagle-import:FA1NDRPPCB8")
      (fields (field (name "MOUSER_PART_NUMBER") "523-FA1-NDRP-PCB-8"))
      (libsource (lib "eagle-import") (part "FA1-NDRP-PCB-8"))
    )
    (comp (ref "J7")
      (value "M50-3600542R")
      (footprint "eagle-import:M503600542R")
      (fields (field (name "MOUSER_PART_NUMBER") "855-M50-3600542R"))
      (libsource (lib "eagle-import") (part "M50-3600542R"))
    )
    (comp (ref "R33")
      (value "1M2")
      (footprint "eagle-import:RESC1005X40N")
      (fields
        (field (name "MANUFACTURER_PART_NUMBER") "CRCW04021M20FKED")
        (field (name "MOUSER_PART_NUMBER") "71-CRCW04021M20FKED")
      )
      (libsource (lib "eagle-import") (part "CRCW04021M20FKED"))
    )
    (comp (ref "R39")
      (value "39R")
      (footprint "eagle-import:RESC1005X40N")
      (fields
        (field (name "MANUFACTURER_PART_NUMBER") "CRCW040239R0FKEDHP")
        (field (name "MOUSER_PART_NUMBER") "71-CRCW040239R0FKEDH")
      )
      (libsource (lib "eagle-import") (part "CRCW040239R0FKEDHP"))
    )
    (comp (ref "R40")
      (value "10k2")
      (footprint "eagle-import:RESC1005X40N")
      (fields
        (field (name "MANUFACTURER_PART_NUMBER") "CRCW040210K2FKED")
        (field (name "MOUSER_PART_NUMBER") "71-CRCW0402-10.2K-E3")
      )
      (libsource (lib "eagle-import") (part "CRCW040210K2FKED"))
    )
    (comp (ref "S1")
      (value "TL4100AF120QG")
      (footprint "eagle-import:TL4100AF120QG")
      (fields (field (name "MOUSER_PART_NUMBER") "612-TL4100AF120QG"))
      (libsource (lib "eagle-import") (part "TL4100AF120QG"))
    )
    (comp (ref "C34")
      (value "100n")
      (footprint "eagle-import:CAPC1005X55N")
      (fields (field (name "MANUFACTURER_PART_NUMBER") "GCM155R71C104KA55J"))
      (libsource (lib "eagle-import") (part "GCM155R71C104KA55J"))
    )
    (comp (ref "C35")
      (value "100n")
      (footprint "eagle-import:CAPC1005X55N")
      (fields (field (name "MANUFACTURER_PART_NUMBER") "GCM155R71C104KA55J"))
      (libsource (lib "eagle-import") (part "GCM155R71C104KA55J"))
    )
    (comp (ref "C52")
      (value "100n")
      (footprint "eagle-import:CAPC1005X55N")
      (fields (field (name "MANUFACTURER_PART_NUMBER") "GCM155R71C104KA55J"))
      (libsource (lib "eagle-import") (part "GCM155R71C104KA55J"))
    )
    (comp (ref "C53")
      (value "100n")
      (footprint "eagle-import:CAPC1005X55N")
      (fields (field (name "MANUFACTURER_PART_NUMBER") "GCM155R71C104KA55J"))
      (libsource (lib "eagle-import") (part "GCM155R71C104KA55J"))
    )
    (comp (ref "D5")
      (value "PESD0402-140")
      (footprint "eagle-import:DIONC1005X43N")
      (libsource (lib "eagle-import") (part "PESD0402-140"))
    )
    (comp (ref "D6")
      (value "PESD0402-140")
      (footprint "eagle-import:DIONC1005X43N")
      (libsource (lib "eagle-import") (part "PESD0402-140"))
    )
    (comp (ref "D7")
      (value "PESD0402-140")
      (footprint "eagle-import:DIONC1005X43N")
      (libsource (lib "eagle-import") (part "PESD0402-140"))
    )
    (comp (ref "D8")
      (value "PESD0402-140")
      (footprint "eagle-import:DIONC1005X43N")
      (libsource (lib "eagle-import") (part "PESD0402-140"))
    )
    (comp (ref "IC9")
      (value "TJA1048TK,118")
      (footprint "eagle-import:SON65P300X450X100-15N")
      (fields (field (name "MOUSER_PART_NUMBER") "771-TJA1048TK118"))
      (libsource (lib "eagle-import") (part "TJA1048TK,118"))
    )
    (comp (ref "IC10")
      (value "MCP2515T-I_ST")
      (footprint "eagle-import:SOP65P640X120-20N")
      (fields
        (field (name "MANUFACTURER_PART_NUMBER") "MCP2515T-I/ST")
        (field (name "MOUSER_PART_NUMBER") "579-MCP2515T-I/ST")
      )
      (libsource (lib "eagle-import") (part "MCP2515T-I_ST"))
    )
    (comp (ref "IC11")
      (value "MCP2515T-I_ST")
      (footprint "eagle-import:SOP65P640X120-20N")
      (fields
        (field (name "MANUFACTURER_PART_NUMBER") "MCP2515T-I/ST")
        (field (name "MOUSER_PART_NUMBER") "579-MCP2515T-I/ST")
      )
      (libsource (lib "eagle-import") (part "MCP2515T-I_ST"))
    )
    (comp (ref "IC12")
      (value "CSTCE16M0V53C-R0")
      (footprint "eagle-import:CSTCE16M0V53CR0")
      (fields (field (name "MOUSER_PART_NUMBER") "81-CSTCE16M0V53C-R0"))
      (libsource (lib "eagle-import") (part "CSTCE16M0V53C-R0"))
    )
    (comp (ref "IC13")
      (value "CSTCE16M0V53C-R0")
      (footprint "eagle-import:CSTCE16M0V53CR0")
      (fields (field (name "MOUSER_PART_NUMBER") "81-CSTCE16M0V53C-R0"))
      (libsource (lib "eagle-import") (part "CSTCE16M0V53C-R0"))
    )
    (comp (ref "R24")
      (value "10k2")
      (footprint "eagle-import:RESC1005X40N")
      (fields
        (field (name "MANUFACTURER_PART_NUMBER") "CRCW040210K2FKED")
        (field (name "MOUSER_PART_NUMBER") "71-CRCW0402-10.2K-E3")
      )
      (libsource (lib "eagle-import") (part "CRCW040210K2FKED"))
    )
    (comp (ref "R25")
      (value "10k2")
      (footprint "eagle-import:RESC1005X40N")
      (fields
        (field (name "MANUFACTURER_PART_NUMBER") "CRCW040210K2FKED")
        (field (name "MOUSER_PART_NUMBER") "71-CRCW0402-10.2K-E3")
      )
      (libsource (lib "eagle-import") (part "CRCW040210K2FKED"))
    )
    (comp (ref "R26")
      (value "10k2")
      (footprint "eagle-import:RESC1005X40N")
      (fields
        (field (name "MANUFACTURER_PART_NUMBER") "CRCW040210K2FKED")
        (field (name "MOUSER_PART_NUMBER") "71-CRCW0402-10.2K-E3")
      )
      (libsource (lib "eagle-import") (part "CRCW040210K2FKED"))
    )
    (comp (ref "R27")
      (value "10k2")
      (footprint "eagle-import:RESC1005X40N")
      (fields
        (field (name "MANUFACTURER_PART_NUMBER") "CRCW040210K2FKED")
        (field (name "MOUSER_PART_NUMBER") "71-CRCW0402-10.2K-E3")
      )
      (libsource (lib "eagle-import") (part "CRCW040210K2FKED"))
    )
    (comp (ref "R28")
      (value "10k2")
      (footprint "eagle-import:RESC1005X40N")
      (fields
        (field (name "MANUFACTURER_PART_NUMBER") "CRCW040210K2FKED")
        (field (name "MOUSER_PART_NUMBER") "71-CRCW0402-10.2K-E3")
      )
      (libsource (lib "eagle-import") (part "CRCW040210K2FKED"))
    )
    (comp (ref "R29")
      (value "10k2")
      (footprint "eagle-import:RESC1005X40N")
      (fields
        (field (name "MANUFACTURER_PART_NUMBER") "CRCW040210K2FKED")
        (field (name "MOUSER_PART_NUMBER") "71-CRCW0402-10.2K-E3")
      )
      (libsource (lib "eagle-import") (part "CRCW040210K2FKED"))
    )
    (comp (ref "R30")
      (value "10k2")
      (footprint "eagle-import:RESC1005X40N")
      (fields
        (field (name "MANUFACTURER_PART_NUMBER") "CRCW040210K2FKED")
        (field (name "MOUSER_PART_NUMBER") "71-CRCW0402-10.2K-E3")
      )
      (libsource (lib "eagle-import") (part "CRCW040210K2FKED"))
    )
    (comp (ref "R31")
      (value "10k2")
      (footprint "eagle-import:RESC1005X40N")
      (fields
        (field (name "MANUFACTURER_PART_NUMBER") "CRCW040210K2FKED")
        (field (name "MOUSER_PART_NUMBER") "71-CRCW0402-10.2K-E3")
      )
      (libsource (lib "eagle-import") (part "CRCW040210K2FKED"))
    )
    (comp (ref "C16")
      (value "20p")
      (footprint "eagle-import:CAPC1005X55N")
      (fields (field (name "MANUFACTURER_PART_NUMBER") "GJM1555C1H200GB01D"))
      (libsource (lib "eagle-import") (part "GJM1555C1H200GB01D"))
    )
    (comp (ref "C17")
      (value "20p")
      (footprint "eagle-import:CAPC1005X55N")
      (fields (field (name "MANUFACTURER_PART_NUMBER") "GJM1555C1H200GB01D"))
      (libsource (lib "eagle-import") (part "GJM1555C1H200GB01D"))
    )
    (comp (ref "C18")
      (value "100n")
      (footprint "eagle-import:CAPC1005X55N")
      (fields (field (name "MANUFACTURER_PART_NUMBER") "GCM155R71C104KA55J"))
      (libsource (lib "eagle-import") (part "GCM155R71C104KA55J"))
    )
    (comp (ref "C19")
      (value "100n")
      (footprint "eagle-import:CAPC1005X55N")
      (fields (field (name "MANUFACTURER_PART_NUMBER") "GCM155R71C104KA55J"))
      (libsource (lib "eagle-import") (part "GCM155R71C104KA55J"))
    )
    (comp (ref "C20")
      (value "10u")
      (footprint "eagle-import:CAPC1608X90N")
      (fields
        (field (name "MANUFACTURER_PART_NUMBER") "GRM188R60J106KE47D")
        (field (name "MOUSER_PART_NUMBER") "81-GRM188R60J106KE7D")
      )
      (libsource (lib "eagle-import") (part "GRM188R60J106KE47D"))
    )
    (comp (ref "C21")
      (value "100n")
      (footprint "eagle-import:CAPC1005X55N")
      (fields (field (name "MANUFACTURER_PART_NUMBER") "GCM155R71C104KA55J"))
      (libsource (lib "eagle-import") (part "GCM155R71C104KA55J"))
    )
    (comp (ref "C22")
      (value "100u")
      (footprint "eagle-import:CAPC3216X180N")
      (fields
        (field (name "MANUFACTURER_PART_NUMBER") "GRM31CD80J107ME39K")
        (field (name "MOUSER_PART_NUMBER") "81-GRM31CD80J107ME9K")
      )
      (libsource (lib "eagle-import") (part "GRM31CD80J107ME39K"))
    )
    (comp (ref "C23")
      (value "10u")
      (footprint "eagle-import:CAPC1608X90N")
      (fields
        (field (name "MANUFACTURER_PART_NUMBER") "GRM188R60J106KE47D")
        (field (name "MOUSER_PART_NUMBER") "81-GRM188R60J106KE7D")
      )
      (libsource (lib "eagle-import") (part "GRM188R60J106KE47D"))
    )
    (comp (ref "C24")
      (value "100n")
      (footprint "eagle-import:CAPC1005X55N")
      (fields (field (name "MANUFACTURER_PART_NUMBER") "GCM155R71C104KA55J"))
      (libsource (lib "eagle-import") (part "GCM155R71C104KA55J"))
    )
    (comp (ref "C25")
      (value "10n")
      (footprint "eagle-import:CAPC1005X55N")
      (fields
        (field (name "MANUFACTURER_PART_NUMBER") "GCM155R71H103KA55D")
        (field (name "MOUSER_PART_NUMBER") "81-GCM155R71H103KA5D")
      )
      (libsource (lib "eagle-import") (part "GCM155R71H103KA55D"))
    )
    (comp (ref "C26")
      (value "68p")
      (footprint "eagle-import:CAPC1005X55N")
      (fields (field (name "MANUFACTURER_PART_NUMBER") "GCM1555C1H680JA16D"))
      (libsource (lib "eagle-import") (part "GCM1555C1H680JA16D"))
    )
    (comp (ref "C27")
      (value "100n")
      (footprint "eagle-import:CAPC1005X55N")
      (fields (field (name "MANUFACTURER_PART_NUMBER") "GCM155R71C104KA55J"))
      (libsource (lib "eagle-import") (part "GCM155R71C104KA55J"))
    )
    (comp (ref "C28")
      (value "15p")
      (footprint "eagle-import:CAPC1005X55N")
      (fields (field (name "MANUFACTURER_PART_NUMBER") "GCM1555C1H150JA16D"))
      (libsource (lib "eagle-import") (part "GCM1555C1H150JA16D"))
    )
    (comp (ref "C29")
      (value "1u")
      (footprint "eagle-import:CAPC1005X55N")
      (fields
        (field (name "MANUFACTURER_PART_NUMBER") "GRM155R61C105MA12D")
        (field (name "MOUSER_PART_NUMBER") "81-GRM155R61C105MA2D")
      )
      (libsource (lib "eagle-import") (part "GRM155R61C105MA12D"))
    )
    (comp (ref "C30")
      (value "100n")
      (footprint "eagle-import:CAPC1005X55N")
      (fields (field (name "MANUFACTURER_PART_NUMBER") "GCM155R71C104KA55J"))
      (libsource (lib "eagle-import") (part "GCM155R71C104KA55J"))
    )
    (comp (ref "C41")
      (value "GRM1555C1H150JA01J")
      (footprint "eagle-import:CAPC1005X55N")
      (fields (field (name "MOUSER_PART_NUMBER") "81-GRM1555C1H150JA1J"))
      (libsource (lib "eagle-import") (part "GRM1555C1H150JA01J"))
    )
    (comp (ref "C42")
      (value "GRM1555C1H330JA01J")
      (footprint "eagle-import:CAPC1005X55N")
      (fields (field (name "MOUSER_PART_NUMBER") "81-GRM1555C1H330JA1J"))
      (libsource (lib "eagle-import") (part "GRM1555C1H330JA01J"))
    )
    (comp (ref "C44")
      (value "100n")
      (footprint "eagle-import:CAPC1005X55N")
      (fields (field (name "MANUFACTURER_PART_NUMBER") "GCM155R71C104KA55J"))
      (libsource (lib "eagle-import") (part "GCM155R71C104KA55J"))
    )
    (comp (ref "C45")
      (value "100n")
      (footprint "eagle-import:CAPC1005X55N")
      (fields (field (name "MANUFACTURER_PART_NUMBER") "GCM155R71C104KA55J"))
      (libsource (lib "eagle-import") (part "GCM155R71C104KA55J"))
    )
    (comp (ref "C46")
      (value "GRM1555C1H470JA01D")
      (footprint "eagle-import:CAPC1005X55N")
      (fields (field (name "MOUSER_PART_NUMBER") "81-GRM1555C1H470JA1D"))
      (libsource (lib "eagle-import") (part "GRM1555C1H470JA01D"))
    )
    (comp (ref "C47")
      (value "GRM1555C1H470JA01D")
      (footprint "eagle-import:CAPC1005X55N")
      (fields (field (name "MOUSER_PART_NUMBER") "81-GRM1555C1H470JA1D"))
      (libsource (lib "eagle-import") (part "GRM1555C1H470JA01D"))
    )
    (comp (ref "C48")
      (value "GRM1555C1H470JA01D")
      (footprint "eagle-import:CAPC1005X55N")
      (fields (field (name "MOUSER_PART_NUMBER") "81-GRM1555C1H470JA1D"))
      (libsource (lib "eagle-import") (part "GRM1555C1H470JA01D"))
    )
    (comp (ref "C49")
      (value "GRM1555C1H470JA01D")
      (footprint "eagle-import:CAPC1005X55N")
      (fields (field (name "MOUSER_PART_NUMBER") "81-GRM1555C1H470JA1D"))
      (libsource (lib "eagle-import") (part "GRM1555C1H470JA01D"))
    )
    (comp (ref "C50")
      (value "10u")
      (footprint "eagle-import:CAPC1608X90N")
      (fields
        (field (name "MANUFACTURER_PART_NUMBER") "GRM188R60J106KE47D")
        (field (name "MOUSER_PART_NUMBER") "81-GRM188R60J106KE7D")
      )
      (libsource (lib "eagle-import") (part "GRM188R60J106KE47D"))
    )
    (comp (ref "D2")
      (value "PESD0402-140")
      (footprint "eagle-import:DIONC1005X43N")
      (libsource (lib "eagle-import") (part "PESD0402-140"))
    )
    (comp (ref "D3")
      (value "PESD0402-140")
      (footprint "eagle-import:DIONC1005X43N")
      (libsource (lib "eagle-import") (part "PESD0402-140"))
    )
    (comp (ref "D4")
      (value "PESD0402-140")
      (footprint "eagle-import:DIONC1005X43N")
      (libsource (lib "eagle-import") (part "PESD0402-140"))
    )
    (comp (ref "D13")
      (value "PESD0402-140")
      (footprint "eagle-import:DIONC1005X43N")
      (libsource (lib "eagle-import") (part "PESD0402-140"))
    )
    (comp (ref "D14")
      (value "PESD0402-140")
      (footprint "eagle-import:DIONC1005X43N")
      (libsource (lib "eagle-import") (part "PESD0402-140"))
    )
    (comp (ref "FB1")
      (value "BLM18PG471SZ1D")
      (footprint "eagle-import:BEADC1608X95N")
      (fields (field (name "MOUSER_PART_NUMBER") "81-BLM18PG471SZ1D"))
      (libsource (lib "eagle-import") (part "BLM18PG471SZ1D"))
    )
    (comp (ref "IC1")
      (value "ATSAMD21G18A-AU")
      (footprint "eagle-import:QFP50P900X900X120-48N")
      (fields (field (name "MOUSER_PART_NUMBER") "556-ATSAMD21G18A-AU"))
      (libsource (lib "eagle-import") (part "ATSAMD21G18A-AU"))
    )
    (comp (ref "IC2")
      (value "SARA-R410M-02B")
      (footprint "eagle-import:SARA-U201-03B")
      (libsource (lib "eagle-import") (part "SARA-R410M-02B"))
    )
    (comp (ref "J1")
      (value "SF56S006V4BR2000")
      (footprint "eagle-import:SF56S006V4BR2000")
      (fields (field (name "MOUSER_PART_NUMBER") "656-SF56S006V4BR2000"))
      (libsource (lib "eagle-import") (part "SF56S006V4BR2000"))
    )
    (comp (ref "L4")
      (value "LQG15HN39NJ02D")
      (footprint "eagle-import:INDC1005X55N")
      (libsource (lib "eagle-import") (part "LQG15HN39NJ02D"))
    )
    (comp (ref "LED3")
      (value "HSMS-C190")
      (footprint "eagle-import:LEDC1608X90N")
      (fields (field (name "MOUSER_PART_NUMBER") "630-HSMS-C190"))
      (libsource (lib "eagle-import") (part "HSMS-C190"))
    )
    (comp (ref "Q3")
      (value "2N7002,215")
      (footprint "eagle-import:SOT95P230X110-3N")
      (fields (field (name "MOUSER_PART_NUMBER") "771-2N7002-T/R"))
      (libsource (lib "eagle-import") (part "2N7002,215"))
    )
    (comp (ref "Q4")
      (value "2N7002DW-7-F")
      (footprint "eagle-import:SOT65P210X100-6N")
      (fields (field (name "MOUSER_PART_NUMBER") "621-2N7002DW-F"))
      (libsource (lib "eagle-import") (part "2N7002DW-7-F"))
    )
    (comp (ref "R14")
      (value "0R")
      (footprint "eagle-import:RESC1005X40N")
      (fields (field (name "MANUFACTURER_PART_NUMBER") "RMCF0402ZT0R00"))
      (libsource (lib "eagle-import") (part "RMCF0402ZT0R00"))
    )
    (comp (ref "R15")
      (value "10k2")
      (footprint "eagle-import:RESC1005X40N")
      (fields
        (field (name "MANUFACTURER_PART_NUMBER") "CRCW040210K2FKED")
        (field (name "MOUSER_PART_NUMBER") "71-CRCW0402-10.2K-E3")
      )
      (libsource (lib "eagle-import") (part "CRCW040210K2FKED"))
    )
    (comp (ref "R16")
      (value "1M2")
      (footprint "eagle-import:RESC1005X40N")
      (fields
        (field (name "MANUFACTURER_PART_NUMBER") "CRCW04021M20FKED")
        (field (name "MOUSER_PART_NUMBER") "71-CRCW04021M20FKED")
      )
      (libsource (lib "eagle-import") (part "CRCW04021M20FKED"))
    )
    (comp (ref "R17")
      (value "1M2")
      (footprint "eagle-import:RESC1005X40N")
      (fields
        (field (name "MANUFACTURER_PART_NUMBER") "CRCW04021M20FKED")
        (field (name "MOUSER_PART_NUMBER") "71-CRCW04021M20FKED")
      )
      (libsource (lib "eagle-import") (part "CRCW04021M20FKED"))
    )
    (comp (ref "R18")
      (value "1M2")
      (footprint "eagle-import:RESC1005X40N")
      (fields
        (field (name "MANUFACTURER_PART_NUMBER") "CRCW04021M20FKED")
        (field (name "MOUSER_PART_NUMBER") "71-CRCW04021M20FKED")
      )
      (libsource (lib "eagle-import") (part "CRCW04021M20FKED"))
    )
    (comp (ref "R19")
      (value "1M2")
      (footprint "eagle-import:RESC1005X40N")
      (fields
        (field (name "MANUFACTURER_PART_NUMBER") "CRCW04021M20FKED")
        (field (name "MOUSER_PART_NUMBER") "71-CRCW04021M20FKED")
      )
      (libsource (lib "eagle-import") (part "CRCW04021M20FKED"))
    )
    (comp (ref "R34")
      (value "0R")
      (footprint "eagle-import:RESC1005X40N")
      (fields (field (name "MANUFACTURER_PART_NUMBER") "RMCF0402ZT0R00"))
      (libsource (lib "eagle-import") (part "RMCF0402ZT0R00"))
    )
    (comp (ref "TP_1V8")
      (value "TPB1,27")
      (footprint "eagle-import:B1,27")
      (libsource (lib "eagle-import") (part "TPB1,27"))
    )
    (comp (ref "TP_MDCD")
      (value "TPB1,27")
      (footprint "eagle-import:B1,27")
      (libsource (lib "eagle-import") (part "TPB1,27"))
    )
    (comp (ref "TP_MPWR_ON")
      (value "TPB1,27")
      (footprint "eagle-import:B1,27")
      (libsource (lib "eagle-import") (part "TPB1,27"))
    )
    (comp (ref "TP_MRST")
      (value "TPB1,27")
      (footprint "eagle-import:B1,27")
      (libsource (lib "eagle-import") (part "TPB1,27"))
    )
    (comp (ref "TP_MRX")
      (value "TPB1,27")
      (footprint "eagle-import:B1,27")
      (libsource (lib "eagle-import") (part "TPB1,27"))
    )
    (comp (ref "TP_MTX")
      (value "TPB1,27")
      (footprint "eagle-import:B1,27")
      (libsource (lib "eagle-import") (part "TPB1,27"))
    )
    (comp (ref "TP_MUSBN")
      (value "TPB1,27")
      (footprint "eagle-import:B1,27")
      (libsource (lib "eagle-import") (part "TPB1,27"))
    )
    (comp (ref "TP_MUSBP")
      (value "TPB1,27")
      (footprint "eagle-import:B1,27")
      (libsource (lib "eagle-import") (part "TPB1,27"))
    )
    (comp (ref "TP_MVUSB")
      (value "TPB1,27")
      (footprint "eagle-import:B1,27")
      (libsource (lib "eagle-import") (part "TPB1,27"))
    )
    (comp (ref "U1")
      (value "SN74AVC2T245RSWR")
      (footprint "eagle-import:RSW(RPUQFNN10)")
      (fields (field (name "MOUSER_PART_NUMBER") "595-SN74AVC2T245RSWR"))
      (libsource (lib "eagle-import") (part "SN74AVC2T245RSWR"))
    )
    (comp (ref "Y1")
      (value "ABS07-32.768KHZ-1-T")
      (footprint "eagle-import:ABS0716632768KHZT")
      (fields
        (field (name "MANUFACTURER_PART_NUMBER") "ABS07-32.768KHz-1-T")
        (field (name "MOUSER_PART_NUMBER") "815-ABS07-32.7K-1-T")
      )
      (libsource (lib "eagle-import") (part "ABS07-32.768KHZ-1-T"))
    )
    (comp (ref "C31")
      (value "100n")
      (footprint "eagle-import:CAPC1005X55N")
      (fields (field (name "MANUFACTURER_PART_NUMBER") "GCM155R71C104KA55J"))
      (libsource (lib "eagle-import") (part "GCM155R71C104KA55J"))
    )
    (comp (ref "C32")
      (value "10u")
      (footprint "eagle-import:CAPC1005X55N")
      (fields
        (field (name "MANUFACTURER_PART_NUMBER") "GRM155C80J106ME11D")
        (field (name "MOUSER_PART_NUMBER") "81-GRM155C80J106ME1D")
      )
      (libsource (lib "eagle-import") (part "GRM155C80J106ME11D"))
    )
    (comp (ref "C33")
      (value "100n")
      (footprint "eagle-import:CAPC1005X55N")
      (fields (field (name "MANUFACTURER_PART_NUMBER") "GCM155R71C104KA55J"))
      (libsource (lib "eagle-import") (part "GCM155R71C104KA55J"))
    )
    (comp (ref "C54")
      (value "100n")
      (footprint "eagle-import:CAPC1005X55N")
      (fields (field (name "MANUFACTURER_PART_NUMBER") "GCM155R71C104KA55J"))
      (libsource (lib "eagle-import") (part "GCM155R71C104KA55J"))
    )
    (comp (ref "D10")
      (value "MBR0560-TP")
      (footprint "eagle-import:SOD3716X135N")
      (fields (field (name "MOUSER_PART_NUMBER") "833-MBR0560-TP"))
      (libsource (lib "eagle-import") (part "MBR0560-TP"))
    )
    (comp (ref "D11")
      (value "MBR0560-TP")
      (footprint "eagle-import:SOD3716X135N")
      (fields (field (name "MOUSER_PART_NUMBER") "833-MBR0560-TP"))
      (libsource (lib "eagle-import") (part "MBR0560-TP"))
    )
    (comp (ref "IC6")
      (value "ATECC508A-MAHDA-T")
      (footprint "eagle-import:SON50P300X200X60-9N")
      (fields (field (name "MOUSER_PART_NUMBER") "556-ATECC508A-MAHDAT"))
      (libsource (lib "eagle-import") (part "ATECC508A-MAHDA-T"))
    )
    (comp (ref "IC7")
      (value "SPBTLE-RF")
      (footprint "eagle-import:XCVR_SPBTLE-RF")
      (fields (field (name "MF") "STMicroelectronics"))
      (libsource (lib "eagle-import") (part "SPBTLE-RF"))
    )
    (comp (ref "IC8")
      (value "W25Q16JVZPIQ")
      (footprint "eagle-import:SON127P600X500X80-9N")
      (fields (field (name "MOUSER_PART_NUMBER") "454-W25Q16JVZPIQ"))
      (libsource (lib "eagle-import") (part "W25Q16JVZPIQ"))
    )
    (comp (ref "J2")
      (value "1040310811")
      (footprint "eagle-import:1040310811")
      (libsource (lib "eagle-import") (part "1040310811"))
    )
    (comp (ref "K1")
      (value "EE2-3TNU-L")
      (footprint "eagle-import:EE25TNU")
      (fields (field (name "MOUSER_PART_NUMBER") "80-EE2-3TNU-L"))
      (libsource (lib "eagle-import") (part "EE2-3TNU-L"))
    )
    (comp (ref "Q1")
      (value "2N7002DW-7-F")
      (footprint "eagle-import:SOT65P210X100-6N")
      (fields (field (name "MOUSER_PART_NUMBER") "621-2N7002DW-F"))
      (libsource (lib "eagle-import") (part "2N7002DW-7-F"))
    )
    (comp (ref "Q5")
      (value "BSP76E6433HUMA1")
      (footprint "eagle-import:SOT230P700X170-4N")
      (libsource (lib "eagle-import") (part "BSP76E6433HUMA1"))
    )
    (comp (ref "Q6")
      (value "BSP76E6433HUMA1")
      (footprint "eagle-import:SOT230P700X170-4N")
      (libsource (lib "eagle-import") (part "BSP76E6433HUMA1"))
    )
    (comp (ref "R11")
      (value "1M2")
      (footprint "eagle-import:RESC1005X40N")
      (fields
        (field (name "MANUFACTURER_PART_NUMBER") "CRCW04021M20FKED")
        (field (name "MOUSER_PART_NUMBER") "71-CRCW04021M20FKED")
      )
      (libsource (lib "eagle-import") (part "CRCW04021M20FKED"))
    )
    (comp (ref "R12")
      (value "1M2")
      (footprint "eagle-import:RESC1005X40N")
      (fields
        (field (name "MANUFACTURER_PART_NUMBER") "CRCW04021M20FKED")
        (field (name "MOUSER_PART_NUMBER") "71-CRCW04021M20FKED")
      )
      (libsource (lib "eagle-import") (part "CRCW04021M20FKED"))
    )
    (comp (ref "R20")
      (value "0R")
      (footprint "eagle-import:RESC3116X65N")
      (fields
        (field (name "MANUFACTURER_PART_NUMBER") "CRG1206ZR")
        (field (name "MOUSER_PART_NUMBER") "279-CRG1206ZR")
      )
      (libsource (lib "eagle-import") (part "CRG1206ZR"))
    )
    (comp (ref "R21")
      (value "0R")
      (footprint "eagle-import:RESC3116X65N")
      (fields
        (field (name "MANUFACTURER_PART_NUMBER") "CRG1206ZR")
        (field (name "MOUSER_PART_NUMBER") "279-CRG1206ZR")
      )
      (libsource (lib "eagle-import") (part "CRG1206ZR"))
    )
    (comp (ref "R22")
      (value "10k2")
      (footprint "eagle-import:RESC1005X40N")
      (fields
        (field (name "MANUFACTURER_PART_NUMBER") "CRCW040210K2FKED")
        (field (name "MOUSER_PART_NUMBER") "71-CRCW0402-10.2K-E3")
      )
      (libsource (lib "eagle-import") (part "CRCW040210K2FKED"))
    )
    (comp (ref "R23")
      (value "10k2")
      (footprint "eagle-import:RESC1005X40N")
      (fields
        (field (name "MANUFACTURER_PART_NUMBER") "CRCW040210K2FKED")
        (field (name "MOUSER_PART_NUMBER") "71-CRCW0402-10.2K-E3")
      )
      (libsource (lib "eagle-import") (part "CRCW040210K2FKED"))
    )
    (comp (ref "R35")
      (value "40k2")
      (footprint "eagle-import:RESC1005X40N")
      (fields
        (field (name "MANUFACTURER_PART_NUMBER") "CRCW040240K2FKED")
        (field (name "MOUSER_PART_NUMBER") "71-CRCW0402-40.2K-E3")
      )
      (libsource (lib "eagle-import") (part "CRCW040240K2FKED"))
    )
    (comp (ref "R36")
      (value "10k2")
      (footprint "eagle-import:RESC1005X40N")
      (fields
        (field (name "MANUFACTURER_PART_NUMBER") "CRCW040210K2FKED")
        (field (name "MOUSER_PART_NUMBER") "71-CRCW0402-10.2K-E3")
      )
      (libsource (lib "eagle-import") (part "CRCW040210K2FKED"))
    )
  )
  (nets
    (net (code "1") (name "+1V8") (class "Default")
      (node (ref "C44") (pin "1") (pinfunction "1_1") (pintype "bidirectional"))
      (node (ref "IC2") (pin "4") (pinfunction "V_INT_4") (pintype "bidirectional"))
      (node (ref "R16") (pin "2") (pinfunction "2_2") (pintype "bidirectional"))
      (node (ref "R17") (pin "2") (pinfunction "2_2") (pintype "bidirectional"))
      (node (ref "TP_1V8") (pin "TP") (pinfunction "TP_TP") (pintype "input"))
      (node (ref "U1") (pin "6") (pinfunction "VCCB_6") (pintype "power_in"))
    )
    (net (code "2") (name "+3V3") (class "Default")
      (node (ref "C18") (pin "2") (pinfunction "2_2") (pintype "bidirectional"))
      (node (ref "C19") (pin "2") (pinfunction "2_2") (pintype "bidirectional"))
      (node (ref "C30") (pin "1") (pinfunction "1_1") (pintype "bidirectional"))
      (node (ref "C31") (pin "2") (pinfunction "2_2") (pintype "bidirectional"))
      (node (ref "C32") (pin "2") (pinfunction "2_2") (pintype "bidirectional"))
      (node (ref "C33") (pin "2") (pinfunction "2_2") (pintype "bidirectional"))
      (node (ref "C34") (pin "2") (pinfunction "2_2") (pintype "bidirectional"))
      (node (ref "C36") (pin "1") (pinfunction "1_1") (pintype "bidirectional"))
      (node (ref "C37") (pin "1") (pinfunction "1_1") (pintype "bidirectional"))
      (node (ref "C45") (pin "2") (pinfunction "2_2") (pintype "bidirectional"))
      (node (ref "C50") (pin "1") (pinfunction "1_1") (pintype "bidirectional"))
      (node (ref "C51") (pin "2") (pinfunction "2_2") (pintype "bidirectional"))
      (node (ref "C52") (pin "1") (pinfunction "1_1") (pintype "bidirectional"))
      (node (ref "C53") (pin "1") (pinfunction "1_1") (pintype "bidirectional"))
      (node (ref "C54") (pin "2") (pinfunction "2_2") (pintype "bidirectional"))
      (node (ref "C8") (pin "2") (pinfunction "2_2") (pintype "bidirectional"))
      (node (ref "D10") (pin "1") (pinfunction "K_1") (pintype "bidirectional"))
      (node (ref "D11") (pin "1") (pinfunction "K_1") (pintype "bidirectional"))
      (node (ref "FB1") (pin "1") (pinfunction "1_1") (pintype "bidirectional"))
      (node (ref "IC1") (pin "17") (pinfunction "VDDIO_1_17") (pintype "bidirectional"))
      (node (ref "IC1") (pin "36") (pinfunction "VDDIO_2_36") (pintype "bidirectional"))
      (node (ref "IC1") (pin "44") (pinfunction "VDDIN_44") (pintype "bidirectional"))
      (node (ref "IC10") (pin "20") (pinfunction "VDD_20") (pintype "bidirectional"))
      (node (ref "IC11") (pin "20") (pinfunction "VDD_20") (pintype "bidirectional"))
      (node (ref "IC3") (pin "5") (pinfunction "VOUT_5") (pintype "bidirectional"))
      (node (ref "IC6") (pin "8") (pinfunction "VCC_8") (pintype "bidirectional"))
      (node (ref "IC7") (pin "5") (pinfunction "VIN_5") (pintype "power_in"))
      (node (ref "IC8") (pin "3") (pinfunction "IO2_3") (pintype "bidirectional"))
      (node (ref "IC8") (pin "7") (pinfunction "IO3_7") (pintype "bidirectional"))
      (node (ref "IC8") (pin "8") (pinfunction "VCC_8") (pintype "bidirectional"))
      (node (ref "IC9") (pin "11") (pinfunction "VIO_11") (pintype "bidirectional"))
      (node (ref "J2") (pin "4") (pinfunction "VDD_4") (pintype "bidirectional"))
      (node (ref "J7") (pin "1") (pinfunction "1_1") (pintype "bidirectional"))
      (node (ref "K1") (pin "1") (pinfunction "SET_COIL_+_1") (pintype "bidirectional"))
      (node (ref "K1") (pin "6") (pinfunction "RESET_COIL_+_6") (pintype "bidirectional"))
      (node (ref "R22") (pin "2") (pinfunction "2_2") (pintype "bidirectional"))
      (node (ref "R23") (pin "2") (pinfunction "2_2") (pintype "bidirectional"))
      (node (ref "R24") (pin "2") (pinfunction "2_2") (pintype "bidirectional"))
      (node (ref "R25") (pin "2") (pinfunction "2_2") (pintype "bidirectional"))
      (node (ref "R26") (pin "2") (pinfunction "2_2") (pintype "bidirectional"))
      (node (ref "R27") (pin "2") (pinfunction "2_2") (pintype "bidirectional"))
      (node (ref "R28") (pin "2") (pinfunction "2_2") (pintype "bidirectional"))
      (node (ref "R29") (pin "2") (pinfunction "2_2") (pintype "bidirectional"))
      (node (ref "R30") (pin "2") (pinfunction "2_2") (pintype "bidirectional"))
      (node (ref "R31") (pin "2") (pinfunction "2_2") (pintype "bidirectional"))
      (node (ref "R32") (pin "2") (pinfunction "2_2") (pintype "bidirectional"))
      (node (ref "R4") (pin "2") (pinfunction "2_2") (pintype "bidirectional"))
      (node (ref "R40") (pin "2") (pinfunction "2_2") (pintype "bidirectional"))
      (node (ref "TP3V3") (pin "TP") (pinfunction "TP_TP") (pintype "input"))
      (node (ref "U$1") (pin "7_VCC_IO") (pinfunction "7_VCC_IO_7_VCC_IO") (pintype "power_in"))
      (node (ref "U$1") (pin "8_VCC") (pinfunction "8_VCC_8_VCC") (pintype "power_in"))
      (node (ref "U1") (pin "10") (pinfunction "DIR1_10") (pintype "bidirectional"))
      (node (ref "U1") (pin "7") (pinfunction "VCCA_7") (pintype "power_in"))
    )
    (net (code "3") (name "+3V8") (class "Default")
      (node (ref "C14") (pin "2") (pinfunction "2_2") (pintype "bidirectional"))
      (node (ref "C15") (pin "2") (pinfunction "2_2") (pintype "bidirectional"))
      (node (ref "C22") (pin "2") (pinfunction "2_2") (pintype "bidirectional"))
      (node (ref "C23") (pin "2") (pinfunction "2_2") (pintype "bidirectional"))
      (node (ref "C24") (pin "2") (pinfunction "2_2") (pintype "bidirectional"))
      (node (ref "C25") (pin "2") (pinfunction "2_2") (pintype "bidirectional"))
      (node (ref "C26") (pin "2") (pinfunction "2_2") (pintype "bidirectional"))
      (node (ref "C28") (pin "2") (pinfunction "2_2") (pintype "bidirectional"))
      (node (ref "C9") (pin "2") (pinfunction "2_2") (pintype "bidirectional"))
      (node (ref "IC2") (pin "51") (pinfunction "VCC_1_51") (pintype "bidirectional"))
      (node (ref "IC2") (pin "52") (pinfunction "VCC_2_52") (pintype "bidirectional"))
      (node (ref "IC2") (pin "53") (pinfunction "VCC_3_53") (pintype "bidirectional"))
      (node (ref "IC3") (pin "1") (pinfunction "VIN_1") (pintype "bidirectional"))
      (node (ref "L2") (pin "2") (pinfunction "2_2") (pintype "bidirectional"))
      (node (ref "R9") (pin "2") (pinfunction "2_2") (pintype "bidirectional"))
      (node (ref "TP3V8") (pin "TP") (pinfunction "TP_TP") (pintype "input"))
    )
    (net (code "4") (name "+12V") (class "Default")
      (node (ref "C1") (pin "2") (pinfunction "2_2") (pintype "bidirectional"))
      (node (ref "C10") (pin "2") (pinfunction "2_2") (pintype "bidirectional"))
      (node (ref "C12") (pin "2") (pinfunction "2_2") (pintype "bidirectional"))
      (node (ref "C13") (pin "2") (pinfunction "2_2") (pintype "bidirectional"))
      (node (ref "C39") (pin "2") (pinfunction "2_2") (pintype "bidirectional"))
      (node (ref "F1") (pin "1") (pinfunction "1_1") (pintype "bidirectional"))
      (node (ref "F2") (pin "1") (pinfunction "1_1") (pintype "bidirectional"))
      (node (ref "IC4") (pin "2") (pinfunction "VIN_2") (pintype "input"))
      (node (ref "IC5") (pin "1") (pinfunction "VIN_1") (pintype "bidirectional"))
      (node (ref "IC5") (pin "5") (pinfunction "EN_5") (pintype "bidirectional"))
      (node (ref "R35") (pin "2") (pinfunction "2_2") (pintype "bidirectional"))
      (node (ref "R8") (pin "2") (pinfunction "2_2") (pintype "bidirectional"))
    )
    (net (code "5") (name "12V_IN") (class "Default")
      (node (ref "F2") (pin "2") (pinfunction "2_2") (pintype "bidirectional"))
      (node (ref "J4") (pin "8") (pinfunction "8_8") (pintype "bidirectional"))
    )
    (net (code "6") (name "12V_OUT") (class "Default")
      (node (ref "F1") (pin "2") (pinfunction "2_2") (pintype "bidirectional"))
      (node (ref "J4") (pin "13") (pinfunction "13_13") (pintype "bidirectional"))
    )
    (net (code "7") (name "CAN0H_OUT") (class "Default")
      (node (ref "D8") (pin "2") (pinfunction "A_2") (pintype "bidirectional"))
      (node (ref "IC9") (pin "13") (pinfunction "CANH1_13") (pintype "bidirectional"))
      (node (ref "J4") (pin "9") (pinfunction "9_9") (pintype "bidirectional"))
    )
    (net (code "8") (name "CAN0L_OUT") (class "Default")
      (node (ref "D7") (pin "2") (pinfunction "A_2") (pintype "bidirectional"))
      (node (ref "IC9") (pin "12") (pinfunction "CANL1_12") (pintype "bidirectional"))
      (node (ref "J4") (pin "2") (pinfunction "2_2") (pintype "bidirectional"))
    )
    (net (code "9") (name "CAN1H_OUT") (class "Default")
      (node (ref "D6") (pin "2") (pinfunction "A_2") (pintype "bidirectional"))
      (node (ref "IC9") (pin "10") (pinfunction "CANH2_10") (pintype "bidirectional"))
      (node (ref "J4") (pin "10") (pinfunction "10_10") (pintype "bidirectional"))
    )
    (net (code "10") (name "CAN1L_OUT") (class "Default")
      (node (ref "D5") (pin "2") (pinfunction "A_2") (pintype "bidirectional"))
      (node (ref "IC9") (pin "9") (pinfunction "CANL2_9") (pintype "bidirectional"))
      (node (ref "J4") (pin "3") (pinfunction "3_3") (pintype "bidirectional"))
    )
    (net (code "11") (name "CODE_A_IN") (class "Default")
      (node (ref "J4") (pin "11") (pinfunction "11_11") (pintype "bidirectional"))
      (node (ref "K1") (pin "4") (pinfunction "COM_1_4") (pintype "bidirectional"))
    )
    (net (code "12") (name "CODE_A_OUT") (class "Default")
      (node (ref "J4") (pin "4") (pinfunction "4_4") (pintype "bidirectional"))
      (node (ref "K1") (pin "5") (pinfunction "NO_1_5") (pintype "bidirectional"))
    )
    (net (code "13") (name "CODE_B_IN") (class "Default")
      (node (ref "J4") (pin "12") (pinfunction "12_12") (pintype "bidirectional"))
      (node (ref "K1") (pin "9") (pinfunction "COM_2_9") (pintype "bidirectional"))
    )
    (net (code "14") (name "CODE_B_OUT") (class "Default")
      (node (ref "J4") (pin "5") (pinfunction "5_5") (pintype "bidirectional"))
      (node (ref "K1") (pin "10") (pinfunction "NC_2_10") (pintype "bidirectional"))
    )
    (net (code "15") (name "GND") (class "Default")
      (node (ref "C1") (pin "1") (pinfunction "1_1") (pintype "bidirectional"))
      (node (ref "C10") (pin "1") (pinfunction "1_1") (pintype "bidirectional"))
      (node (ref "C11") (pin "1") (pinfunction "1_1") (pintype "bidirectional"))
      (node (ref "C12") (pin "1") (pinfunction "1_1") (pintype "bidirectional"))
      (node (ref "C13") (pin "1") (pinfunction "1_1") (pintype "bidirectional"))
      (node (ref "C14") (pin "1") (pinfunction "1_1") (pintype "bidirectional"))
      (node (ref "C15") (pin "1") (pinfunction "1_1") (pintype "bidirectional"))
      (node (ref "C16") (pin "1") (pinfunction "1_1") (pintype "bidirectional"))
      (node (ref "C17") (pin "1") (pinfunction "1_1") (pintype "bidirectional"))
      (node (ref "C18") (pin "1") (pinfunction "1_1") (pintype "bidirectional"))
      (node (ref "C19") (pin "1") (pinfunction "1_1") (pintype "bidirectional"))
      (node (ref "C20") (pin "1") (pinfunction "1_1") (pintype "bidirectional"))
      (node (ref "C21") (pin "1") (pinfunction "1_1") (pintype "bidirectional"))
      (node (ref "C22") (pin "1") (pinfunction "1_1") (pintype "bidirectional"))
      (node (ref "C23") (pin "1") (pinfunction "1_1") (pintype "bidirectional"))
      (node (ref "C24") (pin "1") (pinfunction "1_1") (pintype "bidirectional"))
      (node (ref "C25") (pin "1") (pinfunction "1_1") (pintype "bidirectional"))
      (node (ref "C26") (pin "1") (pinfunction "1_1") (pintype "bidirectional"))
      (node (ref "C27") (pin "1") (pinfunction "1_1") (pintype "bidirectional"))
      (node (ref "C28") (pin "1") (pinfunction "1_1") (pintype "bidirectional"))
      (node (ref "C29") (pin "2") (pinfunction "2_2") (pintype "bidirectional"))
      (node (ref "C3") (pin "1") (pinfunction "1_1") (pintype "bidirectional"))
      (node (ref "C30") (pin "2") (pinfunction "2_2") (pintype "bidirectional"))
      (node (ref "C31") (pin "1") (pinfunction "1_1") (pintype "bidirectional"))
      (node (ref "C32") (pin "1") (pinfunction "1_1") (pintype "bidirectional"))
      (node (ref "C33") (pin "1") (pinfunction "1_1") (pintype "bidirectional"))
      (node (ref "C34") (pin "1") (pinfunction "1_1") (pintype "bidirectional"))
      (node (ref "C35") (pin "2") (pinfunction "2_2") (pintype "bidirectional"))
      (node (ref "C36") (pin "2") (pinfunction "2_2") (pintype "bidirectional"))
      (node (ref "C37") (pin "2") (pinfunction "2_2") (pintype "bidirectional"))
      (node (ref "C39") (pin "1") (pinfunction "1_1") (pintype "bidirectional"))
      (node (ref "C4") (pin "1") (pinfunction "1_1") (pintype "bidirectional"))
      (node (ref "C40") (pin "1") (pinfunction "1_1") (pintype "bidirectional"))
      (node (ref "C43") (pin "2") (pinfunction "2_2") (pintype "bidirectional"))
      (node (ref "C44") (pin "2") (pinfunction "2_2") (pintype "bidirectional"))
      (node (ref "C45") (pin "1") (pinfunction "1_1") (pintype "bidirectional"))
      (node (ref "C46") (pin "1") (pinfunction "1_1") (pintype "bidirectional"))
      (node (ref "C47") (pin "1") (pinfunction "1_1") (pintype "bidirectional"))
      (node (ref "C48") (pin "1") (pinfunction "1_1") (pintype "bidirectional"))
      (node (ref "C49") (pin "1") (pinfunction "1_1") (pintype "bidirectional"))
      (node (ref "C5") (pin "1") (pinfunction "1_1") (pintype "bidirectional"))
      (node (ref "C50") (pin "2") (pinfunction "2_2") (pintype "bidirectional"))
      (node (ref "C52") (pin "2") (pinfunction "2_2") (pintype "bidirectional"))
      (node (ref "C53") (pin "2") (pinfunction "2_2") (pintype "bidirectional"))
      (node (ref "C54") (pin "1") (pinfunction "1_1") (pintype "bidirectional"))
      (node (ref "C6") (pin "1") (pinfunction "1_1") (pintype "bidirectional"))
      (node (ref "C7") (pin "2") (pinfunction "+_2") (pintype "bidirectional"))
      (node (ref "C8") (pin "1") (pinfunction "1_1") (pintype "bidirectional"))
      (node (ref "C9") (pin "1") (pinfunction "1_1") (pintype "bidirectional"))
      (node (ref "D1") (pin "2") (pinfunction "A_2") (pintype "bidirectional"))
      (node (ref "D13") (pin "1") (pinfunction "K_1") (pintype "bidirectional"))
      (node (ref "D14") (pin "1") (pinfunction "K_1") (pintype "bidirectional"))
      (node (ref "D2") (pin "1") (pinfunction "K_1") (pintype "bidirectional"))
      (node (ref "D3") (pin "1") (pinfunction "K_1") (pintype "bidirectional"))
      (node (ref "D4") (pin "1") (pinfunction "K_1") (pintype "bidirectional"))
      (node (ref "D5") (pin "1") (pinfunction "K_1") (pintype "bidirectional"))
      (node (ref "D6") (pin "1") (pinfunction "K_1") (pintype "bidirectional"))
      (node (ref "D7") (pin "1") (pinfunction "K_1") (pintype "bidirectional"))
      (node (ref "D8") (pin "1") (pinfunction "K_1") (pintype "bidirectional"))
      (node (ref "IC1") (pin "18") (pinfunction "GND_1_18") (pintype "bidirectional"))
      (node (ref "IC1") (pin "35") (pinfunction "GND_2_35") (pintype "bidirectional"))
      (node (ref "IC1") (pin "42") (pinfunction "GND_3_42") (pintype "bidirectional"))
      (node (ref "IC1") (pin "5") (pinfunction "GNDANA_5") (pintype "bidirectional"))
      (node (ref "IC10") (pin "10") (pinfunction "VSS_10") (pintype "bidirectional"))
      (node (ref "IC11") (pin "10") (pinfunction "VSS_10") (pintype "bidirectional"))
      (node (ref "IC12") (pin "2") (pinfunction "2_2") (pintype "bidirectional"))
      (node (ref "IC13") (pin "2") (pinfunction "2_2") (pintype "bidirectional"))
      (node (ref "IC2") (pin "1") (pinfunction "GND_1_1") (pintype "bidirectional"))
      (node (ref "IC2") (pin "14") (pinfunction "GND_4_14") (pintype "bidirectional"))
      (node (ref "IC2") (pin "20") (pinfunction "GND_5_20") (pintype "bidirectional"))
      (node (ref "IC2") (pin "21") (pinfunction "GND_6_21") (pintype "bidirectional"))
      (node (ref "IC2") (pin "22") (pinfunction "GND_7_22") (pintype "bidirectional"))
      (node (ref "IC2") (pin "3") (pinfunction "GND_2_3") (pintype "bidirectional"))
      (node (ref "IC2") (pin "30") (pinfunction "GND_8_30") (pintype "bidirectional"))
      (node (ref "IC2") (pin "32") (pinfunction "GND_9_32") (pintype "bidirectional"))
      (node (ref "IC2") (pin "33") (pinfunction "RSVD_3_33") (pintype "bidirectional"))
      (node (ref "IC2") (pin "43") (pinfunction "GND_10_43") (pintype "bidirectional"))
      (node (ref "IC2") (pin "5") (pinfunction "GND_3_5") (pintype "bidirectional"))
      (node (ref "IC2") (pin "50") (pinfunction "GND_11_50") (pintype "bidirectional"))
      (node (ref "IC2") (pin "54") (pinfunction "GND_12_54") (pintype "bidirectional"))
      (node (ref "IC2") (pin "55") (pinfunction "GND_13_55") (pintype "bidirectional"))
      (node (ref "IC2") (pin "57") (pinfunction "GND_14_57") (pintype "bidirectional"))
      (node (ref "IC2") (pin "58") (pinfunction "GND_15_58") (pintype "bidirectional"))
      (node (ref "IC2") (pin "59") (pinfunction "GND_16_59") (pintype "bidirectional"))
      (node (ref "IC2") (pin "60") (pinfunction "GND_17_60") (pintype "bidirectional"))
      (node (ref "IC2") (pin "61") (pinfunction "GND_18_61") (pintype "bidirectional"))
      (node (ref "IC2") (pin "63") (pinfunction "GND_19_63") (pintype "bidirectional"))
      (node (ref "IC2") (pin "64") (pinfunction "GND_20_64") (pintype "bidirectional"))
      (node (ref "IC2") (pin "65") (pinfunction "GND_21_65") (pintype "bidirectional"))
      (node (ref "IC2") (pin "66") (pinfunction "GND_22_66") (pintype "bidirectional"))
      (node (ref "IC2") (pin "67") (pinfunction "GND_23_67") (pintype "bidirectional"))
      (node (ref "IC2") (pin "68") (pinfunction "GND_24_68") (pintype "bidirectional"))
      (node (ref "IC2") (pin "69") (pinfunction "GND_25_69") (pintype "bidirectional"))
      (node (ref "IC2") (pin "70") (pinfunction "GND_26_70") (pintype "bidirectional"))
      (node (ref "IC2") (pin "71") (pinfunction "GND_27_71") (pintype "bidirectional"))
      (node (ref "IC2") (pin "72") (pinfunction "GND_28_72") (pintype "bidirectional"))
      (node (ref "IC2") (pin "73") (pinfunction "GND_29_73") (pintype "bidirectional"))
      (node (ref "IC2") (pin "74") (pinfunction "GND_30_74") (pintype "bidirectional"))
      (node (ref "IC2") (pin "75") (pinfunction "GND_31_75") (pintype "bidirectional"))
      (node (ref "IC2") (pin "76") (pinfunction "GND_32_76") (pintype "bidirectional"))
      (node (ref "IC2") (pin "77") (pinfunction "GND_33_77") (pintype "bidirectional"))
      (node (ref "IC2") (pin "78") (pinfunction "GND_34_78") (pintype "bidirectional"))
      (node (ref "IC2") (pin "79") (pinfunction "GND_35_79") (pintype "bidirectional"))
      (node (ref "IC2") (pin "80") (pinfunction "GND_36_80") (pintype "bidirectional"))
      (node (ref "IC2") (pin "81") (pinfunction "GND_37_81") (pintype "bidirectional"))
      (node (ref "IC2") (pin "82") (pinfunction "GND_38_82") (pintype "bidirectional"))
      (node (ref "IC2") (pin "83") (pinfunction "GND_39_83") (pintype "bidirectional"))
      (node (ref "IC2") (pin "84") (pinfunction "GND_40_84") (pintype "bidirectional"))
      (node (ref "IC2") (pin "85") (pinfunction "GND_41_85") (pintype "bidirectional"))
      (node (ref "IC2") (pin "86") (pinfunction "GND_42_86") (pintype "bidirectional"))
      (node (ref "IC2") (pin "87") (pinfunction "GND_43_87") (pintype "bidirectional"))
      (node (ref "IC2") (pin "88") (pinfunction "GND_44_88") (pintype "bidirectional"))
      (node (ref "IC2") (pin "89") (pinfunction "GND_45_89") (pintype "bidirectional"))
      (node (ref "IC2") (pin "90") (pinfunction "GND_46_90") (pintype "bidirectional"))
      (node (ref "IC2") (pin "91") (pinfunction "GND_47_91") (pintype "bidirectional"))
      (node (ref "IC2") (pin "92") (pinfunction "GND_48_92") (pintype "bidirectional"))
      (node (ref "IC2") (pin "93") (pinfunction "GND_49_93") (pintype "bidirectional"))
      (node (ref "IC2") (pin "94") (pinfunction "GND_50_94") (pintype "bidirectional"))
      (node (ref "IC2") (pin "95") (pinfunction "GND_51_95") (pintype "bidirectional"))
      (node (ref "IC2") (pin "96") (pinfunction "GND_52_96") (pintype "bidirectional"))
      (node (ref "IC3") (pin "2") (pinfunction "GND_2") (pintype "bidirectional"))
      (node (ref "IC4") (pin "7") (pinfunction "GND_7") (pintype "power_in"))
      (node (ref "IC5") (pin "3") (pinfunction "GND_3") (pintype "bidirectional"))
      (node (ref "IC6") (pin "4") (pinfunction "GND_4") (pintype "bidirectional"))
      (node (ref "IC7") (pin "6") (pinfunction "GND_6") (pintype "power_in"))
      (node (ref "IC8") (pin "4") (pinfunction "GND_4") (pintype "bidirectional"))
      (node (ref "IC8") (pin "9") (pinfunction "EP_9") (pintype "bidirectional"))
      (node (ref "IC9") (pin "2") (pinfunction "GNDA_2") (pintype "bidirectional"))
      (node (ref "IC9") (pin "5") (pinfunction "GNDB_5") (pintype "bidirectional"))
      (node (ref "J1") (pin "10") (pinfunction "HD1_10") (pintype "bidirectional"))
      (node (ref "J1") (pin "11") (pinfunction "HD4_11") (pintype "bidirectional"))
      (node (ref "J1") (pin "4") (pinfunction "C5_4") (pintype "bidirectional"))
      (node (ref "J1") (pin "7") (pinfunction "HD3_7") (pintype "bidirectional"))
      (node (ref "J1") (pin "9") (pinfunction "HD2,_DSW1_9") (pintype "bidirectional"))
      (node (ref "J2") (pin "6") (pinfunction "VSS_6") (pintype "bidirectional"))
      (node (ref "J3") (pin "1") (pinfunction "1_1") (pintype "bidirectional"))
      (node (ref "J3") (pin "2") (pinfunction "2_2") (pintype "bidirectional"))
      (node (ref "J3") (pin "3") (pinfunction "3_3") (pintype "bidirectional"))
      (node (ref "J3") (pin "4") (pinfunction "4_4") (pintype "bidirectional"))
      (node (ref "J4") (pin "1") (pinfunction "1_1") (pintype "bidirectional"))
      (node (ref "J4") (pin "6") (pinfunction "6_6") (pintype "bidirectional"))
      (node (ref "J5") (pin "5") (pinfunction "5_5") (pintype "passive"))
      (node (ref "J6") (pin "1") (pinfunction "1_1") (pintype "bidirectional"))
      (node (ref "J6") (pin "2") (pinfunction "2_2") (pintype "bidirectional"))
      (node (ref "J6") (pin "3") (pinfunction "3_3") (pintype "bidirectional"))
      (node (ref "J6") (pin "4") (pinfunction "4_4") (pintype "bidirectional"))
      (node (ref "J7") (pin "3") (pinfunction "3_3") (pintype "bidirectional"))
      (node (ref "J7") (pin "5") (pinfunction "5_5") (pintype "bidirectional"))
      (node (ref "J7") (pin "9") (pinfunction "9_9") (pintype "bidirectional"))
      (node (ref "L4") (pin "1") (pinfunction "1_1") (pintype "bidirectional"))
      (node (ref "LED1") (pin "1") (pinfunction "K_1") (pintype "bidirectional"))
      (node (ref "LED3") (pin "1") (pinfunction "K_1") (pintype "bidirectional"))
      (node (ref "Q1") (pin "1") (pinfunction "S1_1") (pintype "bidirectional"))
      (node (ref "Q1") (pin "4") (pinfunction "S2_4") (pintype "bidirectional"))
      (node (ref "Q2") (pin "2") (pinfunction "2_2") (pintype "bidirectional"))
      (node (ref "Q3") (pin "2") (pinfunction "2_2") (pintype "bidirectional"))
      (node (ref "Q4") (pin "1") (pinfunction "S1_1") (pintype "bidirectional"))
      (node (ref "Q4") (pin "4") (pinfunction "S2_4") (pintype "bidirectional"))
      (node (ref "Q5") (pin "3") (pinfunction "S_3") (pintype "power_in"))
      (node (ref "Q6") (pin "3") (pinfunction "S_3") (pintype "power_in"))
      (node (ref "R10") (pin "1") (pinfunction "1_1") (pintype "bidirectional"))
      (node (ref "R11") (pin "1") (pinfunction "1_1") (pintype "bidirectional"))
      (node (ref "R12") (pin "1") (pinfunction "1_1") (pintype "bidirectional"))
      (node (ref "R14") (pin "2") (pinfunction "2_2") (pintype "bidirectional"))
      (node (ref "R18") (pin "1") (pinfunction "1_1") (pintype "bidirectional"))
      (node (ref "R19") (pin "1") (pinfunction "1_1") (pintype "bidirectional"))
      (node (ref "R2") (pin "1") (pinfunction "1_1") (pintype "bidirectional"))
      (node (ref "R33") (pin "1") (pinfunction "1_1") (pintype "bidirectional"))
      (node (ref "R36") (pin "1") (pinfunction "1_1") (pintype "bidirectional"))
      (node (ref "R6") (pin "1") (pinfunction "1_1") (pintype "bidirectional"))
      (node (ref "R7") (pin "1") (pinfunction "1_1") (pintype "bidirectional"))
      (node (ref "S1") (pin "1") (pinfunction "1_1") (pintype "bidirectional"))
      (node (ref "S1") (pin "3") (pinfunction "CHASSIS_PCB_PAD_1_3") (pintype "bidirectional"))
      (node (ref "S1") (pin "4") (pinfunction "CHASSIS_PCB_PAD_2_4") (pintype "bidirectional"))
      (node (ref "U$1") (pin "10_GND") (pinfunction "10_GND_10_GND") (pintype "power_in"))
      (node (ref "U$1") (pin "12_GND") (pinfunction "12_GND_12_GND") (pintype "power_in"))
      (node (ref "U$1") (pin "1_GND") (pinfunction "1_GND_1_GND") (pintype "power_in"))
      (node (ref "U1") (pin "1") (pinfunction "DIR2_1") (pintype "bidirectional"))
      (node (ref "U1") (pin "2") (pinfunction "~{OE2}_2") (pintype "bidirectional"))
      (node (ref "U1") (pin "3") (pinfunction "GND_3") (pintype "power_in"))
    )
    (net (code "16") (name "GPS_ANT") (class "Default")
      (node (ref "J3") (pin "5") (pinfunction "5_5") (pintype "bidirectional"))
      (node (ref "L3") (pin "2") (pinfunction "2_2") (pintype "bidirectional"))
      (node (ref "U$1") (pin "11_RF_IN") (pinfunction "11_RF_IN_11_RF_IN") (pintype "bidirectional"))
    )
    (net (code "17") (name "GPS_BCKP") (class "Default")
      (node (ref "R5") (pin "1") (pinfunction "1_1") (pintype "bidirectional"))
      (node (ref "U$1") (pin "6_V_BCKP") (pinfunction "6_V_BCKP_6_V_BCKP") (pintype "bidirectional"))
    )
    (net (code "18") (name "GRST") (class "Default")
      (node (ref "Q2") (pin "3") (pinfunction "3_3") (pintype "bidirectional"))
      (node (ref "U$1") (pin "9_RESET_N") (pinfunction "9_V_RESET_N_9_RESET_N") (pintype "power_in"))
    )
    (net (code "19") (name "G_SCL") (class "Default")
      (node (ref "R38") (pin "2") (pinfunction "2_2") (pintype "passive"))
      (node (ref "U$1") (pin "17_SCL") (pinfunction "17_SCL_17_SCL") (pintype "bidirectional"))
    )
    (net (code "20") (name "G_SDA") (class "Default")
      (node (ref "R37") (pin "2") (pinfunction "2_2") (pintype "passive"))
      (node (ref "U$1") (pin "16_SDA") (pinfunction "16_SDA_16_SDA") (pintype "bidirectional"))
    )
    (net (code "21") (name "LOCK_OUT") (class "Default")
      (node (ref "J4") (pin "14") (pinfunction "14_14") (pintype "bidirectional"))
      (node (ref "R20") (pin "2") (pinfunction "2_2") (pintype "bidirectional"))
    )
    (net (code "22") (name "MCTS") (class "Default")
      (node (ref "IC2") (pin "11") (pinfunction "CTS_11") (pintype "bidirectional"))
      (node (ref "R34") (pin "1") (pinfunction "1_1") (pintype "bidirectional"))
    )
    (net (code "23") (name "MDTR") (class "Default")
      (node (ref "IC2") (pin "9") (pinfunction "DTR_9") (pintype "bidirectional"))
      (node (ref "R14") (pin "1") (pinfunction "1_1") (pintype "bidirectional"))
    )
    (net (code "24") (name "MRI") (class "Default")
      (node (ref "IC2") (pin "7") (pinfunction "RI_7") (pintype "bidirectional"))
    )
    (net (code "25") (name "MRST") (class "Default")
      (node (ref "IC2") (pin "18") (pinfunction "RESET_N_18") (pintype "bidirectional"))
      (node (ref "Q4") (pin "3") (pinfunction "D2_3") (pintype "bidirectional"))
      (node (ref "TP_MRST") (pin "TP") (pinfunction "TP_TP") (pintype "input"))
    )
    (net (code "26") (name "MRTS") (class "Default")
      (node (ref "IC2") (pin "10") (pinfunction "RTS_10") (pintype "bidirectional"))
      (node (ref "R34") (pin "2") (pinfunction "2_2") (pintype "bidirectional"))
    )
    (net (code "27") (name "MRX") (class "Default")
      (node (ref "IC2") (pin "13") (pinfunction "RXD_13") (pintype "bidirectional"))
      (node (ref "TP_MRX") (pin "TP") (pinfunction "TP_TP") (pintype "input"))
      (node (ref "U1") (pin "4") (pinfunction "B2_4") (pintype "bidirectional"))
    )
    (net (code "28") (name "MTX") (class "Default")
      (node (ref "IC2") (pin "12") (pinfunction "TXD_12") (pintype "bidirectional"))
      (node (ref "TP_MTX") (pin "TP") (pinfunction "TP_TP") (pintype "input"))
      (node (ref "U1") (pin "5") (pinfunction "B1_5") (pintype "bidirectional"))
    )
    (net (code "29") (name "M_ANT_OUT") (class "Default")
      (node (ref "C42") (pin "2") (pinfunction "2_2") (pintype "bidirectional"))
      (node (ref "J6") (pin "5") (pinfunction "5_5") (pintype "bidirectional"))
    )
    (net (code "30") (name "M_SCL") (class "Default")
      (node (ref "IC2") (pin "27") (pinfunction "SCL_27") (pintype "bidirectional"))
      (node (ref "R38") (pin "1") (pinfunction "1_1") (pintype "passive"))
    )
    (net (code "31") (name "M_SDA") (class "Default")
      (node (ref "IC2") (pin "26") (pinfunction "SDA_26") (pintype "bidirectional"))
      (node (ref "R37") (pin "1") (pinfunction "1_1") (pintype "passive"))
    )
    (net (code "32") (name "M_USB_N") (class "Default")
      (node (ref "IC2") (pin "28") (pinfunction "USB_D-_28") (pintype "bidirectional"))
      (node (ref "TP_MUSBN") (pin "TP") (pinfunction "TP_TP") (pintype "input"))
    )
    (net (code "33") (name "M_USB_P") (class "Default")
      (node (ref "IC2") (pin "29") (pinfunction "USB_D+_29") (pintype "bidirectional"))
      (node (ref "TP_MUSBP") (pin "TP") (pinfunction "TP_TP") (pintype "input"))
    )
    (net (code "34") (name "M_VUSB") (class "Default")
      (node (ref "IC2") (pin "17") (pinfunction "VUSB_DET_17") (pintype "bidirectional"))
      (node (ref "TP_MVUSB") (pin "TP") (pinfunction "TP_TP") (pintype "input"))
    )
    (net (code "35") (name "Net-(C4-Pad2)") (class "Default")
      (node (ref "C4") (pin "2") (pinfunction "2_2") (pintype "bidirectional"))
      (node (ref "R3") (pin "1") (pinfunction "1_1") (pintype "bidirectional"))
    )
    (net (code "36") (name "Net-(C7--)") (class "Default")
      (node (ref "C7") (pin "1") (pinfunction "-_1") (pintype "bidirectional"))
      (node (ref "D9") (pin "1") (pinfunction "K_1") (pintype "bidirectional"))
      (node (ref "R5") (pin "2") (pinfunction "2_2") (pintype "bidirectional"))
    )
    (net (code "37") (name "Net-(C40-Pad2)") (class "Default")
      (node (ref "C40") (pin "2") (pinfunction "2_2") (pintype "bidirectional"))
      (node (ref "L3") (pin "1") (pinfunction "1_1") (pintype "bidirectional"))
      (node (ref "R13") (pin "1") (pinfunction "1_1") (pintype "bidirectional"))
    )
    (net (code "38") (name "Net-(C41-Pad2)") (class "Default")
      (node (ref "C41") (pin "2") (pinfunction "2_2") (pintype "bidirectional"))
      (node (ref "C42") (pin "1") (pinfunction "1_1") (pintype "bidirectional"))
      (node (ref "L4") (pin "2") (pinfunction "2_2") (pintype "bidirectional"))
    )
    (net (code "39") (name "Net-(C43-Pad1)") (class "Default")
      (node (ref "C43") (pin "1") (pinfunction "1_1") (pintype "bidirectional"))
      (node (ref "D12") (pin "1") (pinfunction "1_1") (pintype "passive"))
      (node (ref "J5") (pin "10") (pinfunction "SH_10") (pintype "passive"))
      (node (ref "J5") (pin "11") (pinfunction "SH_11") (pintype "passive"))
      (node (ref "J5") (pin "6") (pinfunction "SH_6") (pintype "passive"))
      (node (ref "J5") (pin "7") (pinfunction "SH_7") (pintype "passive"))
      (node (ref "J5") (pin "8") (pinfunction "SH_8") (pintype "passive"))
      (node (ref "J5") (pin "9") (pinfunction "SH_9") (pintype "passive"))
      (node (ref "R33") (pin "2") (pinfunction "2_2") (pintype "bidirectional"))
    )
    (net (code "40") (name "Net-(D1-K)") (class "Default")
      (node (ref "C2") (pin "1") (pinfunction "1_1") (pintype "bidirectional"))
      (node (ref "D1") (pin "1") (pinfunction "K_1") (pintype "bidirectional"))
      (node (ref "IC4") (pin "8") (pinfunction "PH_8") (pintype "bidirectional"))
      (node (ref "L1") (pin "1") (pinfunction "1_1") (pintype "bidirectional"))
    )
    (net (code "41") (name "Net-(D9-A)") (class "Default")
      (node (ref "D9") (pin "2") (pinfunction "A_2") (pintype "bidirectional"))
      (node (ref "R4") (pin "1") (pinfunction "1_1") (pintype "bidirectional"))
    )
    (net (code "42") (name "Net-(D10-A)") (class "Default")
      (node (ref "D10") (pin "2") (pinfunction "A_2") (pintype "bidirectional"))
      (node (ref "K1") (pin "12") (pinfunction "SET_COIL_-_12") (pintype "bidirectional"))
      (node (ref "Q1") (pin "6") (pinfunction "D1_6") (pintype "bidirectional"))
    )
    (net (code "43") (name "Net-(D11-A)") (class "Default")
      (node (ref "D11") (pin "2") (pinfunction "A_2") (pintype "bidirectional"))
      (node (ref "K1") (pin "7") (pinfunction "RESET_COIL_-_7") (pintype "bidirectional"))
      (node (ref "Q1") (pin "3") (pinfunction "D2_3") (pintype "bidirectional"))
    )
    (net (code "44") (name "Net-(D12-Pad4)") (class "Default")
      (node (ref "D12") (pin "4") (pinfunction "4_4") (pintype "passive"))
      (node (ref "J5") (pin "1") (pinfunction "1_1") (pintype "passive"))
    )
    (net (code "45") (name "Net-(IC1-VDDANA)") (class "Default")
      (node (ref "C20") (pin "2") (pinfunction "2_2") (pintype "bidirectional"))
      (node (ref "C21") (pin "2") (pinfunction "2_2") (pintype "bidirectional"))
      (node (ref "FB1") (pin "2") (pinfunction "2_2") (pintype "bidirectional"))
      (node (ref "IC1") (pin "6") (pinfunction "VDDANA_6") (pintype "bidirectional"))
    )
    (net (code "46") (name "Net-(IC1-VDDCORE)") (class "Default")
      (node (ref "C29") (pin "1") (pinfunction "1_1") (pintype "bidirectional"))
      (node (ref "IC1") (pin "43") (pinfunction "VDDCORE_43") (pintype "bidirectional"))
    )
    (net (code "47") (name "Net-(IC2-ANT)") (class "Default")
      (node (ref "C41") (pin "1") (pinfunction "1_1") (pintype "bidirectional"))
      (node (ref "IC2") (pin "56") (pinfunction "ANT_56") (pintype "bidirectional"))
    )
    (net (code "48") (name "Net-(IC2-DCD)") (class "Default")
      (node (ref "IC2") (pin "8") (pinfunction "DCD_8") (pintype "bidirectional"))
      (node (ref "TP_MDCD") (pin "TP") (pinfunction "TP_TP") (pintype "input"))
    )
    (net (code "49") (name "Net-(IC2-GPIO1)") (class "Default")
      (node (ref "IC2") (pin "16") (pinfunction "GPIO1_16") (pintype "bidirectional"))
      (node (ref "R15") (pin "2") (pinfunction "2_2") (pintype "bidirectional"))
    )
    (net (code "50") (name "Net-(IC4-BOOT)") (class "Default")
      (node (ref "C2") (pin "2") (pinfunction "2_2") (pintype "bidirectional"))
      (node (ref "IC4") (pin "1") (pinfunction "BOOT_1") (pintype "bidirectional"))
    )
    (net (code "51") (name "Net-(IC4-COMP)") (class "Default")
      (node (ref "C3") (pin "2") (pinfunction "2_2") (pintype "bidirectional"))
      (node (ref "IC4") (pin "6") (pinfunction "COMP_6") (pintype "output"))
      (node (ref "R3") (pin "2") (pinfunction "2_2") (pintype "bidirectional"))
    )
    (net (code "52") (name "Net-(IC4-EN)") (class "Default")
      (node (ref "IC4") (pin "3") (pinfunction "EN_3") (pintype "bidirectional"))
      (node (ref "R7") (pin "2") (pinfunction "2_2") (pintype "bidirectional"))
      (node (ref "R8") (pin "1") (pinfunction "1_1") (pintype "bidirectional"))
    )
    (net (code "53") (name "Net-(IC4-SS)") (class "Default")
      (node (ref "C5") (pin "2") (pinfunction "2_2") (pintype "bidirectional"))
      (node (ref "IC4") (pin "4") (pinfunction "SS_4") (pintype "output"))
    )
    (net (code "54") (name "Net-(IC4-VSENSE)") (class "Default")
      (node (ref "IC4") (pin "5") (pinfunction "VSENSE_5") (pintype "bidirectional"))
      (node (ref "R1") (pin "1") (pinfunction "1_1") (pintype "bidirectional"))
      (node (ref "R2") (pin "2") (pinfunction "2_2") (pintype "bidirectional"))
    )
    (net (code "55") (name "Net-(IC5-BST)") (class "Default")
      (node (ref "C38") (pin "2") (pinfunction "2_2") (pintype "bidirectional"))
      (node (ref "IC5") (pin "4") (pinfunction "BST_4") (pintype "bidirectional"))
    )
    (net (code "56") (name "Net-(IC5-FB)") (class "Default")
      (node (ref "IC5") (pin "6") (pinfunction "FB_6") (pintype "bidirectional"))
      (node (ref "R10") (pin "2") (pinfunction "2_2") (pintype "bidirectional"))
      (node (ref "R9") (pin "1") (pinfunction "1_1") (pintype "bidirectional"))
    )
    (net (code "57") (name "Net-(IC5-SW)") (class "Default")
      (node (ref "C38") (pin "1") (pinfunction "1_1") (pintype "bidirectional"))
      (node (ref "IC5") (pin "2") (pinfunction "SW_2") (pintype "bidirectional"))
      (node (ref "L2") (pin "1") (pinfunction "1_1") (pintype "bidirectional"))
    )
    (net (code "58") (name "Net-(IC9-STBN1)") (class "Default")
      (node (ref "IC9") (pin "14") (pinfunction "STBN1_14") (pintype "bidirectional"))
      (node (ref "R30") (pin "1") (pinfunction "1_1") (pintype "bidirectional"))
    )
    (net (code "59") (name "Net-(IC9-STBN2)") (class "Default")
      (node (ref "IC9") (pin "8") (pinfunction "STBN2_8") (pintype "bidirectional"))
      (node (ref "R31") (pin "1") (pinfunction "1_1") (pintype "bidirectional"))
    )
    (net (code "60") (name "Net-(IC10-OSC1)") (class "Default")
      (node (ref "IC10") (pin "9") (pinfunction "OSC1_9") (pintype "bidirectional"))
      (node (ref "IC12") (pin "1") (pinfunction "1_1") (pintype "bidirectional"))
    )
    (net (code "61") (name "Net-(IC10-OSC2)") (class "Default")
      (node (ref "IC10") (pin "8") (pinfunction "OSC2_8") (pintype "bidirectional"))
      (node (ref "IC12") (pin "3") (pinfunction "3_3") (pintype "bidirectional"))
    )
    (net (code "62") (name "Net-(IC10-~{RESET})") (class "Default")
      (node (ref "IC10") (pin "19") (pinfunction "~{RESET}_19") (pintype "bidirectional"))
      (node (ref "R27") (pin "1") (pinfunction "1_1") (pintype "bidirectional"))
    )
    (net (code "63") (name "Net-(IC11-OSC1)") (class "Default")
      (node (ref "IC11") (pin "9") (pinfunction "OSC1_9") (pintype "bidirectional"))
      (node (ref "IC13") (pin "1") (pinfunction "1_1") (pintype "bidirectional"))
    )
    (net (code "64") (name "Net-(IC11-OSC2)") (class "Default")
      (node (ref "IC11") (pin "8") (pinfunction "OSC2_8") (pintype "bidirectional"))
      (node (ref "IC13") (pin "3") (pinfunction "3_3") (pintype "bidirectional"))
    )
    (net (code "65") (name "Net-(IC11-~{RESET})") (class "Default")
      (node (ref "IC11") (pin "19") (pinfunction "~{RESET}_19") (pintype "bidirectional"))
      (node (ref "R25") (pin "1") (pinfunction "1_1") (pintype "bidirectional"))
    )
    (net (code "66") (name "Net-(J7-Pad10)") (class "Default")
      (node (ref "J7") (pin "10") (pinfunction "10_10") (pintype "bidirectional"))
      (node (ref "R39") (pin "1") (pinfunction "1_1") (pintype "bidirectional"))
    )
    (net (code "67") (name "Net-(LED1-A)") (class "Default")
      (node (ref "LED1") (pin "2") (pinfunction "A_2") (pintype "bidirectional"))
      (node (ref "R41") (pin "1") (pinfunction "1_1") (pintype "bidirectional"))
    )
    (net (code "68") (name "Net-(LED3-A)") (class "Default")
      (node (ref "LED3") (pin "2") (pinfunction "A_2") (pintype "bidirectional"))
      (node (ref "R15") (pin "1") (pinfunction "1_1") (pintype "bidirectional"))
    )
    (net (code "69") (name "Net-(LED4-A)") (class "Default")
      (node (ref "LED4") (pin "2") (pinfunction "A_2") (pintype "bidirectional"))
      (node (ref "U$1") (pin "4_TIMEPULSE") (pinfunction "4_TIMEPULSE_4_TIMEPULSE") (pintype "bidirectional"))
    )
    (net (code "70") (name "Net-(LED4-K)") (class "Default")
      (node (ref "LED4") (pin "1") (pinfunction "K_1") (pintype "bidirectional"))
      (node (ref "R32") (pin "1") (pinfunction "1_1") (pintype "bidirectional"))
    )
    (net (code "71") (name "Net-(Q5-D_1)") (class "Default")
      (node (ref "Q5") (pin "2") (pinfunction "D_1_2") (pintype "power_in"))
      (node (ref "Q5") (pin "4") (pinfunction "D_2_4") (pintype "power_in"))
      (node (ref "R20") (pin "1") (pinfunction "1_1") (pintype "bidirectional"))
    )
    (net (code "72") (name "Net-(Q6-D_1)") (class "Default")
      (node (ref "Q6") (pin "2") (pinfunction "D_1_2") (pintype "power_in"))
      (node (ref "Q6") (pin "4") (pinfunction "D_2_4") (pintype "power_in"))
      (node (ref "R21") (pin "1") (pinfunction "1_1") (pintype "bidirectional"))
    )
    (net (code "73") (name "Net-(R13-Pad2)") (class "Default")
      (node (ref "R13") (pin "2") (pinfunction "2_2") (pintype "bidirectional"))
      (node (ref "U$1") (pin "14_VCC_RF") (pinfunction "14_VCC_RF_14_VCC_RF") (pintype "bidirectional"))
    )
    (net (code "74") (name "PA00_XIN32") (class "Default")
      (node (ref "C16") (pin "2") (pinfunction "2_2") (pintype "bidirectional"))
      (node (ref "IC1") (pin "1") (pinfunction "PA00_1") (pintype "bidirectional"))
      (node (ref "Y1") (pin "2") (pinfunction "2_2") (pintype "bidirectional"))
    )
    (net (code "75") (name "PA01_XOUT32") (class "Default")
      (node (ref "C17") (pin "2") (pinfunction "2_2") (pintype "bidirectional"))
      (node (ref "IC1") (pin "2") (pinfunction "PA01_2") (pintype "bidirectional"))
      (node (ref "Y1") (pin "1") (pinfunction "1_1") (pintype "bidirectional"))
    )
    (net (code "76") (name "PA02_C1_SS") (class "Default")
      (node (ref "IC1") (pin "3") (pinfunction "PA02_3") (pintype "bidirectional"))
      (node (ref "IC11") (pin "18") (pinfunction "~{CS}_18") (pintype "bidirectional"))
      (node (ref "R24") (pin "1") (pinfunction "1_1") (pintype "bidirectional"))
    )
    (net (code "77") (name "PA03_VREFA") (class "Default")
      (node (ref "IC1") (pin "4") (pinfunction "PA03_4") (pintype "bidirectional"))
    )
    (net (code "78") (name "PA04_BT_RST") (class "Default")
      (node (ref "IC1") (pin "9") (pinfunction "PA04_9") (pintype "bidirectional"))
      (node (ref "IC7") (pin "11") (pinfunction "BT_RESET_11") (pintype "input"))
    )
    (net (code "79") (name "PA05_AIN5_LOCK") (class "Default")
      (node (ref "IC1") (pin "10") (pinfunction "PA05_10") (pintype "bidirectional"))
      (node (ref "Q5") (pin "1") (pinfunction "IN_1") (pintype "input"))
    )
    (net (code "80") (name "PA06_AIN6_UNLOCK") (class "Default")
      (node (ref "IC1") (pin "11") (pinfunction "PA06_11") (pintype "bidirectional"))
      (node (ref "Q6") (pin "1") (pinfunction "IN_1") (pintype "input"))
    )
    (net (code "81") (name "PA07_C1_INT") (class "Default")
      (node (ref "IC1") (pin "12") (pinfunction "PA07_12") (pintype "bidirectional"))
      (node (ref "IC11") (pin "13") (pinfunction "~{INT}_13") (pintype "bidirectional"))
      (node (ref "R29") (pin "1") (pinfunction "1_1") (pintype "bidirectional"))
    )
    (net (code "82") (name "PA08_S0_I2C_SDA") (class "Default")
      (node (ref "IC1") (pin "13") (pinfunction "PA08_13") (pintype "bidirectional"))
      (node (ref "IC6") (pin "5") (pinfunction "SDA_5") (pintype "bidirectional"))
    )
    (net (code "83") (name "PA09_S0_I2C_SCL") (class "Default")
      (node (ref "IC1") (pin "14") (pinfunction "PA09_14") (pintype "bidirectional"))
      (node (ref "IC6") (pin "6") (pinfunction "SCL_6") (pintype "bidirectional"))
    )
    (net (code "84") (name "PA10_TCC0-W2_VIN") (class "Default")
      (node (ref "IC1") (pin "15") (pinfunction "PA10_15") (pintype "bidirectional"))
      (node (ref "R35") (pin "1") (pinfunction "1_1") (pintype "bidirectional"))
      (node (ref "R36") (pin "2") (pinfunction "2_2") (pintype "bidirectional"))
    )
    (net (code "85") (name "PA11_C0_SS") (class "Default")
      (node (ref "IC1") (pin "16") (pinfunction "PA11_16") (pintype "bidirectional"))
      (node (ref "IC10") (pin "18") (pinfunction "~{CS}_18") (pintype "bidirectional"))
      (node (ref "R26") (pin "1") (pinfunction "1_1") (pintype "bidirectional"))
    )
    (net (code "86") (name "PA12_S2_TX") (class "Default")
      (node (ref "IC1") (pin "21") (pinfunction "PA12_21") (pintype "bidirectional"))
      (node (ref "U1") (pin "8") (pinfunction "A1_8") (pintype "bidirectional"))
    )
    (net (code "87") (name "PA13_S2_RX") (class "Default")
      (node (ref "IC1") (pin "22") (pinfunction "PA13_22") (pintype "bidirectional"))
      (node (ref "U1") (pin "9") (pinfunction "A2_9") (pintype "bidirectional"))
    )
    (net (code "88") (name "PA14_IMM_OFF") (class "Default")
      (node (ref "IC1") (pin "23") (pinfunction "PA14_23") (pintype "bidirectional"))
      (node (ref "Q1") (pin "5") (pinfunction "G2_5") (pintype "input"))
      (node (ref "R12") (pin "2") (pinfunction "2_2") (pintype "bidirectional"))
    )
    (net (code "89") (name "PA15_IMM_ON") (class "Default")
      (node (ref "IC1") (pin "24") (pinfunction "PA15_24") (pintype "bidirectional"))
      (node (ref "Q1") (pin "2") (pinfunction "G1_2") (pintype "input"))
      (node (ref "R11") (pin "2") (pinfunction "2_2") (pintype "bidirectional"))
    )
    (net (code "90") (name "PA16_S1_MOSI") (class "Default")
      (node (ref "IC1") (pin "25") (pinfunction "PA16_25") (pintype "bidirectional"))
      (node (ref "IC10") (pin "16") (pinfunction "SI_16") (pintype "bidirectional"))
      (node (ref "IC11") (pin "16") (pinfunction "SI_16") (pintype "bidirectional"))
      (node (ref "IC8") (pin "5") (pinfunction "DI_(IO0)_5") (pintype "bidirectional"))
      (node (ref "J2") (pin "3") (pinfunction "CMD_3") (pintype "bidirectional"))
    )
    (net (code "91") (name "PA17_S1_SCK") (class "Default")
      (node (ref "IC1") (pin "26") (pinfunction "PA17_26") (pintype "bidirectional"))
      (node (ref "IC10") (pin "14") (pinfunction "SCK_14") (pintype "bidirectional"))
      (node (ref "IC11") (pin "14") (pinfunction "SCK_14") (pintype "bidirectional"))
      (node (ref "IC8") (pin "6") (pinfunction "CLK_6") (pintype "bidirectional"))
      (node (ref "J2") (pin "5") (pinfunction "CLK_5") (pintype "bidirectional"))
    )
    (net (code "92") (name "PA18_OTG") (class "Default")
      (node (ref "IC1") (pin "27") (pinfunction "PA18_27") (pintype "bidirectional"))
      (node (ref "J5") (pin "4") (pinfunction "4_4") (pintype "passive"))
    )
    (net (code "93") (name "PA19_S1_MISO") (class "Default")
      (node (ref "IC1") (pin "28") (pinfunction "PA19_28") (pintype "bidirectional"))
      (node (ref "IC10") (pin "17") (pinfunction "SO_17") (pintype "bidirectional"))
      (node (ref "IC11") (pin "17") (pinfunction "SO_17") (pintype "bidirectional"))
      (node (ref "IC8") (pin "2") (pinfunction "DO_(IO1)_2") (pintype "bidirectional"))
      (node (ref "J2") (pin "7") (pinfunction "DAT0_7") (pintype "bidirectional"))
    )
    (net (code "94") (name "PA20_S2_MISO") (class "Default")
      (node (ref "IC1") (pin "29") (pinfunction "PA20_29") (pintype "bidirectional"))
      (node (ref "IC7") (pin "8") (pinfunction "SPI_MISO_8") (pintype "output"))
    )
    (net (code "95") (name "PA21_C0_INT") (class "Default")
      (node (ref "IC1") (pin "30") (pinfunction "PA21_30") (pintype "bidirectional"))
      (node (ref "IC10") (pin "13") (pinfunction "~{INT}_13") (pintype "bidirectional"))
      (node (ref "R28") (pin "1") (pinfunction "1_1") (pintype "bidirectional"))
    )
    (net (code "96") (name "PA22_S2_MOSI") (class "Default")
      (node (ref "IC1") (pin "31") (pinfunction "PA22_31") (pintype "bidirectional"))
      (node (ref "IC7") (pin "9") (pinfunction "SPI_MOSI_9") (pintype "input"))
    )
    (net (code "97") (name "PA23_S2_SCK") (class "Default")
      (node (ref "IC1") (pin "32") (pinfunction "PA23_32") (pintype "bidirectional"))
      (node (ref "IC7") (pin "7") (pinfunction "SPI_CLK_7") (pintype "input"))
    )
    (net (code "98") (name "PA24_USB_N") (class "Default")
      (node (ref "D12") (pin "3") (pinfunction "3_3") (pintype "passive"))
      (node (ref "IC1") (pin "33") (pinfunction "PA24_33") (pintype "bidirectional"))
      (node (ref "J5") (pin "2") (pinfunction "2_2") (pintype "passive"))
    )
    (net (code "99") (name "PA25_USB_P") (class "Default")
      (node (ref "D12") (pin "2") (pinfunction "2_2") (pintype "passive"))
      (node (ref "IC1") (pin "34") (pinfunction "PA25_34") (pintype "bidirectional"))
      (node (ref "J5") (pin "3") (pinfunction "3_3") (pintype "passive"))
    )
    (net (code "100") (name "PA27_GRST") (class "Default")
      (node (ref "IC1") (pin "39") (pinfunction "PA27_39") (pintype "bidirectional"))
      (node (ref "Q2") (pin "1") (pinfunction "1_1") (pintype "bidirectional"))
      (node (ref "R6") (pin "2") (pinfunction "2_2") (pintype "bidirectional"))
    )
    (net (code "101") (name "PA28_M_PWRON") (class "Default")
      (node (ref "IC1") (pin "41") (pinfunction "PA28_41") (pintype "bidirectional"))
      (node (ref "Q4") (pin "2") (pinfunction "G1_2") (pintype "input"))
      (node (ref "R18") (pin "2") (pinfunction "2_2") (pintype "bidirectional"))
    )
    (net (code "102") (name "PA30_SWCLK") (class "Default")
      (node (ref "IC1") (pin "45") (pinfunction "PA30_45") (pintype "bidirectional"))
      (node (ref "J7") (pin "4") (pinfunction "4_4") (pintype "bidirectional"))
    )
    (net (code "103") (name "PA31_SWDIO") (class "Default")
      (node (ref "IC1") (pin "46") (pinfunction "PA31_46") (pintype "bidirectional"))
      (node (ref "J7") (pin "2") (pinfunction "2_2") (pintype "bidirectional"))
    )
    (net (code "104") (name "PB02_BT_SS") (class "Default")
      (node (ref "IC1") (pin "47") (pinfunction "PB02_47") (pintype "bidirectional"))
      (node (ref "IC7") (pin "10") (pinfunction "SPI_CS_10") (pintype "input"))
    )
    (net (code "105") (name "PB03_BT_IRQ") (class "Default")
      (node (ref "IC1") (pin "48") (pinfunction "PB03_48") (pintype "bidirectional"))
      (node (ref "IC7") (pin "4") (pinfunction "SPI_IRQ_4") (pintype "output"))
    )
    (net (code "106") (name "PB08_M_RST") (class "Default")
      (node (ref "IC1") (pin "7") (pinfunction "PB08_7") (pintype "bidirectional"))
      (node (ref "Q4") (pin "5") (pinfunction "G2_5") (pintype "input"))
      (node (ref "R19") (pin "2") (pinfunction "2_2") (pintype "bidirectional"))
    )
    (net (code "107") (name "PB09") (class "Default")
      (node (ref "IC1") (pin "8") (pinfunction "PB09_8") (pintype "bidirectional"))
      (node (ref "R41") (pin "2") (pinfunction "2_2") (pintype "bidirectional"))
    )
    (net (code "108") (name "PB10_SD_SS") (class "Default")
      (node (ref "IC1") (pin "19") (pinfunction "PB10_19") (pintype "bidirectional"))
      (node (ref "J2") (pin "2") (pinfunction "CD/DAT3_2") (pintype "bidirectional"))
      (node (ref "R23") (pin "1") (pinfunction "1_1") (pintype "bidirectional"))
    )
    (net (code "109") (name "PB11_FL_SS") (class "Default")
      (node (ref "IC1") (pin "20") (pinfunction "PB11_20") (pintype "bidirectional"))
      (node (ref "IC8") (pin "1") (pinfunction "~{CS}_1") (pintype "bidirectional"))
      (node (ref "R22") (pin "1") (pinfunction "1_1") (pintype "bidirectional"))
    )
    (net (code "110") (name "PB22_S5_TX") (class "Default")
      (node (ref "FB2") (pin "2") (pinfunction "2_2") (pintype "bidirectional"))
      (node (ref "IC1") (pin "37") (pinfunction "PB22_37") (pintype "bidirectional"))
    )
    (net (code "111") (name "PB23_S5_RX") (class "Default")
      (node (ref "FB3") (pin "2") (pinfunction "2_2") (pintype "bidirectional"))
      (node (ref "IC1") (pin "38") (pinfunction "PB23_38") (pintype "bidirectional"))
    )
    (net (code "112") (name "PWR_ON") (class "Default")
      (node (ref "IC2") (pin "15") (pinfunction "PWR_ON_15") (pintype "bidirectional"))
      (node (ref "Q4") (pin "6") (pinfunction "D1_6") (pintype "bidirectional"))
      (node (ref "TP_MPWR_ON") (pin "TP") (pinfunction "TP_TP") (pintype "input"))
    )
    (net (code "113") (name "RESETN") (class "Default")
      (node (ref "C51") (pin "1") (pinfunction "1_1") (pintype "bidirectional"))
      (node (ref "IC1") (pin "40") (pinfunction "~{RESET}_40") (pintype "bidirectional"))
      (node (ref "R39") (pin "2") (pinfunction "2_2") (pintype "bidirectional"))
      (node (ref "R40") (pin "1") (pinfunction "1_1") (pintype "bidirectional"))
      (node (ref "S1") (pin "2") (pinfunction "2_2") (pintype "bidirectional"))
    )
    (net (code "114") (name "RXCAN0") (class "Default")
      (node (ref "IC10") (pin "2") (pinfunction "RXCAN_2") (pintype "bidirectional"))
      (node (ref "IC9") (pin "4") (pinfunction "RXD1_4") (pintype "bidirectional"))
    )
    (net (code "115") (name "RXCAN1") (class "Default")
      (node (ref "IC11") (pin "2") (pinfunction "RXCAN_2") (pintype "bidirectional"))
      (node (ref "IC9") (pin "7") (pinfunction "RXD2_7") (pintype "bidirectional"))
    )
    (net (code "116") (name "SCLK") (class "Default")
      (node (ref "C48") (pin "2") (pinfunction "2_2") (pintype "bidirectional"))
      (node (ref "D2") (pin "2") (pinfunction "A_2") (pintype "bidirectional"))
      (node (ref "IC2") (pin "38") (pinfunction "SIM_CLK_38") (pintype "bidirectional"))
      (node (ref "J1") (pin "3") (pinfunction "C3_3") (pintype "bidirectional"))
    )
    (net (code "117") (name "SIM_DET") (class "Default")
      (node (ref "IC2") (pin "42") (pinfunction "GPIO5_42") (pintype "bidirectional"))
      (node (ref "Q3") (pin "3") (pinfunction "3_3") (pintype "bidirectional"))
      (node (ref "R17") (pin "1") (pinfunction "1_1") (pintype "bidirectional"))
    )
    (net (code "118") (name "SIO") (class "Default")
      (node (ref "C47") (pin "2") (pinfunction "2_2") (pintype "bidirectional"))
      (node (ref "D3") (pin "2") (pinfunction "A_2") (pintype "bidirectional"))
      (node (ref "IC2") (pin "39") (pinfunction "SIM_IO_39") (pintype "bidirectional"))
      (node (ref "J1") (pin "6") (pinfunction "C7_6") (pintype "bidirectional"))
    )
    (net (code "119") (name "SRST") (class "Default")
      (node (ref "C46") (pin "2") (pinfunction "2_2") (pintype "bidirectional"))
      (node (ref "D4") (pin "2") (pinfunction "A_2") (pintype "bidirectional"))
      (node (ref "IC2") (pin "40") (pinfunction "SIM_RST_40") (pintype "bidirectional"))
      (node (ref "J1") (pin "2") (pinfunction "C2_2") (pintype "bidirectional"))
    )
    (net (code "120") (name "SSW") (class "Default")
      (node (ref "D14") (pin "2") (pinfunction "A_2") (pintype "bidirectional"))
      (node (ref "J1") (pin "8") (pinfunction "DSW2_8") (pintype "bidirectional"))
      (node (ref "Q3") (pin "1") (pinfunction "1_1") (pintype "bidirectional"))
      (node (ref "R16") (pin "1") (pinfunction "1_1") (pintype "bidirectional"))
    )
    (net (code "121") (name "SVCC") (class "Default")
      (node (ref "C27") (pin "2") (pinfunction "2_2") (pintype "bidirectional"))
      (node (ref "C49") (pin "2") (pinfunction "2_2") (pintype "bidirectional"))
      (node (ref "D13") (pin "2") (pinfunction "A_2") (pintype "bidirectional"))
      (node (ref "IC2") (pin "41") (pinfunction "VSIM_41") (pintype "bidirectional"))
      (node (ref "J1") (pin "1") (pinfunction "C1_1") (pintype "bidirectional"))
    )
    (net (code "122") (name "TXCAN0") (class "Default")
      (node (ref "IC10") (pin "1") (pinfunction "TXCAN_1") (pintype "bidirectional"))
      (node (ref "IC9") (pin "1") (pinfunction "TXD1_1") (pintype "bidirectional"))
    )
    (net (code "123") (name "TXCAN1") (class "Default")
      (node (ref "IC11") (pin "1") (pinfunction "TXCAN_1") (pintype "bidirectional"))
      (node (ref "IC9") (pin "6") (pinfunction "TXD2_6") (pintype "bidirectional"))
    )
    (net (code "124") (name "UB_GPS_RX") (class "Default")
      (node (ref "FB2") (pin "1") (pinfunction "1_1") (pintype "bidirectional"))
      (node (ref "U$1") (pin "3_RXD") (pinfunction "3_RXD_3_RXD") (pintype "bidirectional"))
    )
    (net (code "125") (name "UB_GPS_TX") (class "Default")
      (node (ref "FB3") (pin "1") (pinfunction "1_1") (pintype "bidirectional"))
      (node (ref "U$1") (pin "2_TXD") (pinfunction "2_TXD_2_TXD") (pintype "bidirectional"))
    )
    (net (code "126") (name "UNLOCK_OUT") (class "Default")
      (node (ref "J4") (pin "7") (pinfunction "7_7") (pintype "bidirectional"))
      (node (ref "R21") (pin "2") (pinfunction "2_2") (pintype "bidirectional"))
    )
    (net (code "127") (name "VIN") (class "Default")
      (node (ref "C11") (pin "2") (pinfunction "2_2") (pintype "bidirectional"))
      (node (ref "C35") (pin "1") (pinfunction "1_1") (pintype "bidirectional"))
      (node (ref "C6") (pin "2") (pinfunction "2_2") (pintype "bidirectional"))
      (node (ref "IC9") (pin "3") (pinfunction "VCC_3") (pintype "bidirectional"))
      (node (ref "L1") (pin "2") (pinfunction "2_2") (pintype "bidirectional"))
      (node (ref "R1") (pin "2") (pinfunction "2_2") (pintype "bidirectional"))
      (node (ref "TP5V") (pin "TP") (pinfunction "TP_TP") (pintype "input"))
    )
    (net (code "128") (name "unconnected-(IC2-ANT_DET-Pad62)") (class "Default")
      (node (ref "IC2") (pin "62") (pinfunction "ANT_DET_62") (pintype "bidirectional"))
    )
    (net (code "129") (name "unconnected-(IC2-GPIO2-Pad23)") (class "Default")
      (node (ref "IC2") (pin "23") (pinfunction "GPIO2_23") (pintype "bidirectional"))
    )
    (net (code "130") (name "unconnected-(IC2-GPIO3-Pad24)") (class "Default")
      (node (ref "IC2") (pin "24") (pinfunction "GPIO3_24") (pintype "bidirectional"))
    )
    (net (code "131") (name "unconnected-(IC2-GPIO4-Pad25)") (class "Default")
      (node (ref "IC2") (pin "25") (pinfunction "GPIO4_25") (pintype "bidirectional"))
    )
    (net (code "132") (name "unconnected-(IC2-GPIO6-Pad19)") (class "Default")
      (node (ref "IC2") (pin "19") (pinfunction "GPIO6_19") (pintype "bidirectional"))
    )
    (net (code "133") (name "unconnected-(IC2-I2S_CLK_{slash}_SPI_CLK-Pad36)") (class "Default")
      (node (ref "IC2") (pin "36") (pinfunction "I2S_CLK_/_SPI_CLK_36") (pintype "bidirectional"))
    )
    (net (code "134") (name "unconnected-(IC2-I2S_RXD_{slash}_SPI_MISO-Pad37)") (class "Default")
      (node (ref "IC2") (pin "37") (pinfunction "I2S_RXD_/_SPI_MISO_37") (pintype "bidirectional"))
    )
    (net (code "135") (name "unconnected-(IC2-I2S_TXD_{slash}_SPI_CS-Pad35)") (class "Default")
      (node (ref "IC2") (pin "35") (pinfunction "I2S_TXD_/_SPI_CS_35") (pintype "bidirectional"))
    )
    (net (code "136") (name "unconnected-(IC2-I2S_WA_{slash}_SPI_MOSI-Pad34)") (class "Default")
      (node (ref "IC2") (pin "34") (pinfunction "I2S_WA_/_SPI_MOSI_34") (pintype "bidirectional"))
    )
    (net (code "137") (name "unconnected-(IC2-RSR-Pad6)") (class "Default")
      (node (ref "IC2") (pin "6") (pinfunction "RSR_6") (pintype "bidirectional"))
    )
    (net (code "138") (name "unconnected-(IC2-RSVD_1-Pad2)") (class "Default")
      (node (ref "IC2") (pin "2") (pinfunction "RSVD_1_2") (pintype "bidirectional"))
    )
    (net (code "139") (name "unconnected-(IC2-RSVD_2-Pad31)") (class "Default")
      (node (ref "IC2") (pin "31") (pinfunction "RSVD_2_31") (pintype "bidirectional"))
    )
    (net (code "140") (name "unconnected-(IC2-SDIO_CLK-Pad45)") (class "Default")
      (node (ref "IC2") (pin "45") (pinfunction "SDIO_CLK_45") (pintype "bidirectional"))
    )
    (net (code "141") (name "unconnected-(IC2-SDIO_CMD-Pad46)") (class "Default")
      (node (ref "IC2") (pin "46") (pinfunction "SDIO_CMD_46") (pintype "bidirectional"))
    )
    (net (code "142") (name "unconnected-(IC2-SDIO_D0-Pad47)") (class "Default")
      (node (ref "IC2") (pin "47") (pinfunction "SDIO_D0_47") (pintype "bidirectional"))
    )
    (net (code "143") (name "unconnected-(IC2-SDIO_D1-Pad49)") (class "Default")
      (node (ref "IC2") (pin "49") (pinfunction "SDIO_D1_49") (pintype "bidirectional"))
    )
    (net (code "144") (name "unconnected-(IC2-SDIO_D2-Pad44)") (class "Default")
      (node (ref "IC2") (pin "44") (pinfunction "SDIO_D2_44") (pintype "bidirectional"))
    )
    (net (code "145") (name "unconnected-(IC2-SDIO_D3-Pad48)") (class "Default")
      (node (ref "IC2") (pin "48") (pinfunction "SDIO_D3_48") (pintype "bidirectional"))
    )
    (net (code "146") (name "unconnected-(IC3-ADJ{slash}NC-Pad4)") (class "Default")
      (node (ref "IC3") (pin "4") (pinfunction "ADJ/NC_4") (pintype "bidirectional"))
    )
    (net (code "147") (name "unconnected-(IC3-EN-Pad3)") (class "Default")
      (node (ref "IC3") (pin "3") (pinfunction "EN_3") (pintype "bidirectional"))
    )
    (net (code "148") (name "unconnected-(IC6-EP-Pad9)") (class "Default")
      (node (ref "IC6") (pin "9") (pinfunction "EP_9") (pintype "bidirectional"))
    )
    (net (code "149") (name "unconnected-(IC6-NC_1-Pad1)") (class "Default")
      (node (ref "IC6") (pin "1") (pinfunction "NC_1_1") (pintype "bidirectional"))
    )
    (net (code "150") (name "unconnected-(IC6-NC_2-Pad2)") (class "Default")
      (node (ref "IC6") (pin "2") (pinfunction "NC_2_2") (pintype "bidirectional"))
    )
    (net (code "151") (name "unconnected-(IC6-NC_3-Pad3)") (class "Default")
      (node (ref "IC6") (pin "3") (pinfunction "NC_3_3") (pintype "bidirectional"))
    )
    (net (code "152") (name "unconnected-(IC6-NC_4-Pad7)") (class "Default")
      (node (ref "IC6") (pin "7") (pinfunction "NC_4_7") (pintype "bidirectional"))
    )
    (net (code "153") (name "unconnected-(IC7-ANATEST0-Pad3)") (class "Default")
      (node (ref "IC7") (pin "3") (pinfunction "ANATEST0_3") (pintype "input"))
    )
    (net (code "154") (name "unconnected-(IC7-EXT_LPCLK-Pad1)") (class "Default")
      (node (ref "IC7") (pin "1") (pinfunction "EXT_LPCLK_1") (pintype "input"))
    )
    (net (code "155") (name "unconnected-(IC7-GPIO2-Pad2)") (class "Default")
      (node (ref "IC7") (pin "2") (pinfunction "GPIO2_2") (pintype "bidirectional"))
    )
    (net (code "156") (name "unconnected-(IC9-EP-Pad15)") (class "Default")
      (node (ref "IC9") (pin "15") (pinfunction "EP_15") (pintype "bidirectional"))
    )
    (net (code "157") (name "unconnected-(IC10-CLKOUT{slash}SOF-Pad3)") (class "Default")
      (node (ref "IC10") (pin "3") (pinfunction "CLKOUT/SOF_3") (pintype "bidirectional"))
    )
    (net (code "158") (name "unconnected-(IC10-NC_1-Pad6)") (class "Default")
      (node (ref "IC10") (pin "6") (pinfunction "NC_1_6") (pintype "bidirectional"))
    )
    (net (code "159") (name "unconnected-(IC10-NC_2-Pad15)") (class "Default")
      (node (ref "IC10") (pin "15") (pinfunction "NC_2_15") (pintype "bidirectional"))
    )
    (net (code "160") (name "unconnected-(IC10-~{RX0BF}-Pad12)") (class "Default")
      (node (ref "IC10") (pin "12") (pinfunction "~{RX0BF}_12") (pintype "bidirectional"))
    )
    (net (code "161") (name "unconnected-(IC10-~{RX1BF}-Pad11)") (class "Default")
      (node (ref "IC10") (pin "11") (pinfunction "~{RX1BF}_11") (pintype "bidirectional"))
    )
    (net (code "162") (name "unconnected-(IC10-~{TX0RTS}-Pad4)") (class "Default")
      (node (ref "IC10") (pin "4") (pinfunction "~{TX0RTS}_4") (pintype "bidirectional"))
    )
    (net (code "163") (name "unconnected-(IC10-~{TX1RTS}-Pad5)") (class "Default")
      (node (ref "IC10") (pin "5") (pinfunction "~{TX1RTS}_5") (pintype "bidirectional"))
    )
    (net (code "164") (name "unconnected-(IC10-~{TX2RTS}-Pad7)") (class "Default")
      (node (ref "IC10") (pin "7") (pinfunction "~{TX2RTS}_7") (pintype "bidirectional"))
    )
    (net (code "165") (name "unconnected-(IC11-CLKOUT{slash}SOF-Pad3)") (class "Default")
      (node (ref "IC11") (pin "3") (pinfunction "CLKOUT/SOF_3") (pintype "bidirectional"))
    )
    (net (code "166") (name "unconnected-(IC11-NC_1-Pad6)") (class "Default")
      (node (ref "IC11") (pin "6") (pinfunction "NC_1_6") (pintype "bidirectional"))
    )
    (net (code "167") (name "unconnected-(IC11-NC_2-Pad15)") (class "Default")
      (node (ref "IC11") (pin "15") (pinfunction "NC_2_15") (pintype "bidirectional"))
    )
    (net (code "168") (name "unconnected-(IC11-~{RX0BF}-Pad12)") (class "Default")
      (node (ref "IC11") (pin "12") (pinfunction "~{RX0BF}_12") (pintype "bidirectional"))
    )
    (net (code "169") (name "unconnected-(IC11-~{RX1BF}-Pad11)") (class "Default")
      (node (ref "IC11") (pin "11") (pinfunction "~{RX1BF}_11") (pintype "bidirectional"))
    )
    (net (code "170") (name "unconnected-(IC11-~{TX0RTS}-Pad4)") (class "Default")
      (node (ref "IC11") (pin "4") (pinfunction "~{TX0RTS}_4") (pintype "bidirectional"))
    )
    (net (code "171") (name "unconnected-(IC11-~{TX1RTS}-Pad5)") (class "Default")
      (node (ref "IC11") (pin "5") (pinfunction "~{TX1RTS}_5") (pintype "bidirectional"))
    )
    (net (code "172") (name "unconnected-(IC11-~{TX2RTS}-Pad7)") (class "Default")
      (node (ref "IC11") (pin "7") (pinfunction "~{TX2RTS}_7") (pintype "bidirectional"))
    )
    (net (code "173") (name "unconnected-(J1-C6-Pad5)") (class "Default")
      (node (ref "J1") (pin "5") (pinfunction "C6_5") (pintype "bidirectional"))
    )
    (net (code "174") (name "unconnected-(J2-DAT1-Pad8)") (class "Default")
      (node (ref "J2") (pin "8") (pinfunction "DAT1_8") (pintype "bidirectional"))
    )
    (net (code "175") (name "unconnected-(J2-DAT2-Pad1)") (class "Default")
      (node (ref "J2") (pin "1") (pinfunction "DAT2_1") (pintype "bidirectional"))
    )
    (net (code "176") (name "unconnected-(J7-Pad6)") (class "Default")
      (node (ref "J7") (pin "6") (pinfunction "6_6") (pintype "bidirectional"))
    )
    (net (code "177") (name "unconnected-(J7-Pad7)") (class "Default")
      (node (ref "J7") (pin "7") (pinfunction "7_7") (pintype "bidirectional"))
    )
    (net (code "178") (name "unconnected-(J7-Pad8)") (class "Default")
      (node (ref "J7") (pin "8") (pinfunction "8_8") (pintype "bidirectional"))
    )
    (net (code "179") (name "unconnected-(K1-NC_1-Pad3)") (class "Default")
      (node (ref "K1") (pin "3") (pinfunction "NC_1_3") (pintype "bidirectional"))
    )
    (net (code "180") (name "unconnected-(K1-NO_2-Pad8)") (class "Default")
      (node (ref "K1") (pin "8") (pinfunction "NO_2_8") (pintype "bidirectional"))
    )
    (net (code "181") (name "unconnected-(U$1-13_LNA_EN{slash}RES-Pad13_LNA_EN)") (class "Default")
      (node (ref "U$1") (pin "13_LNA_EN") (pinfunction "13_LNA_EN/RES_13_LNA_EN") (pintype "bidirectional"))
    )
    (net (code "182") (name "unconnected-(U$1-15_RES{slash}V_ANT-Pad15_V_ANT{slash}RESERVED)") (class "Default")
      (node (ref "U$1") (pin "15_V_ANT/RESERVED") (pinfunction "15_RES/V_ANT_15_V_ANT/RESERVED") (pintype "bidirectional"))
    )
    (net (code "183") (name "unconnected-(U$1-Pad5_EXTINT)") (class "Default")
      (node (ref "U$1") (pin "5_EXTINT") (pinfunction "5_EXTINT_5_EXTINT") (pintype "bidirectional"))
    )
    (net (code "184") (name "unconnected-(U$1-Pad18_SAFEBOOT_N)") (class "Default")
      (node (ref "U$1") (pin "18_SAFEBOOT_N") (pinfunction "18_SAFEBOOT_N_18_SAFEBOOT_N") (pintype "bidirectional"))
    )
  )
)
